# RadioBerry.net
KiCad netlist of a schematic drawn in EAGLE
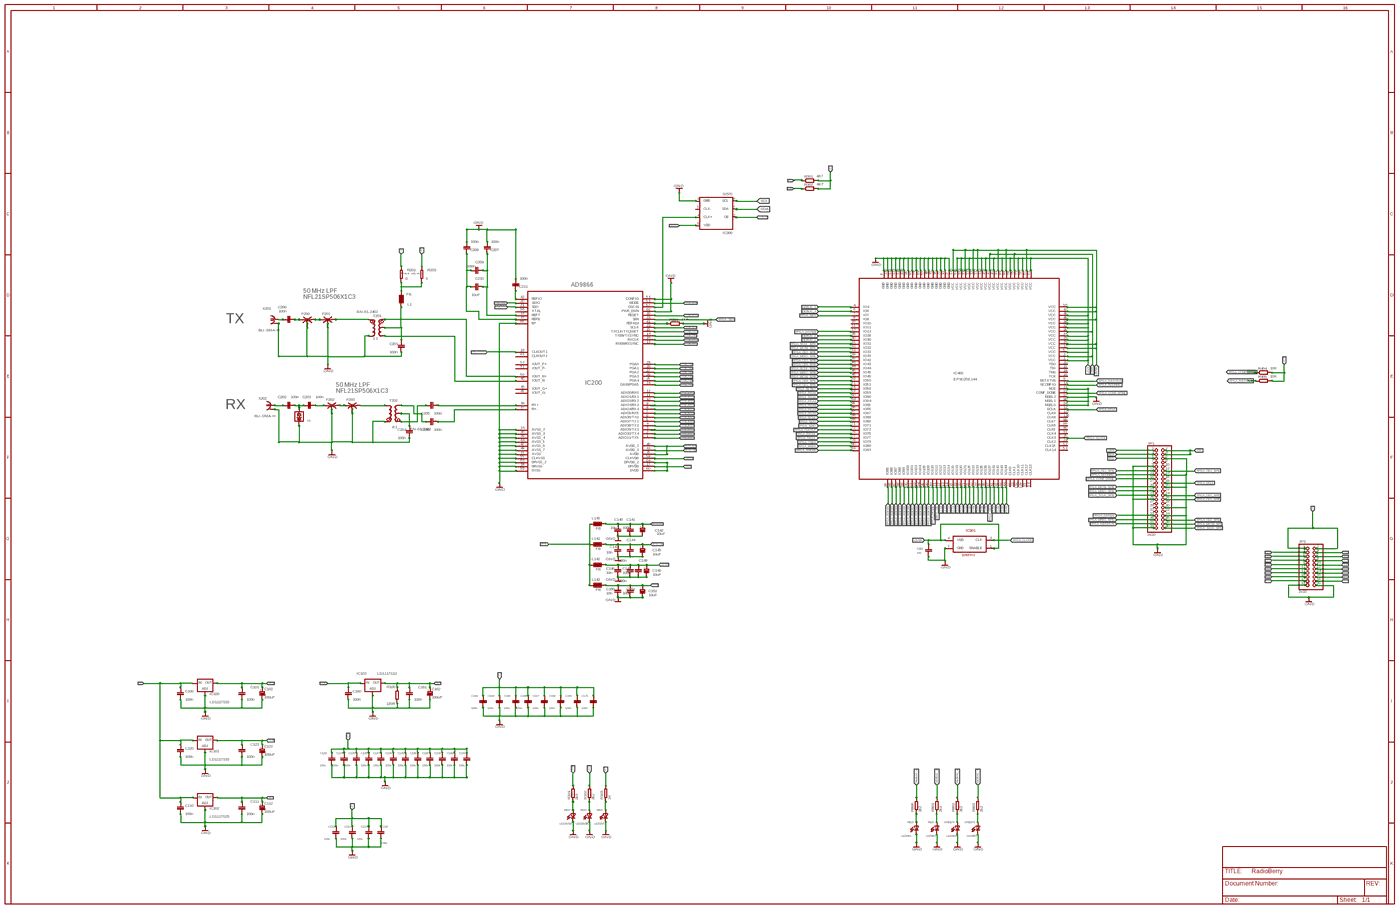
[diagram p0: schematic, sheet 1, overview]
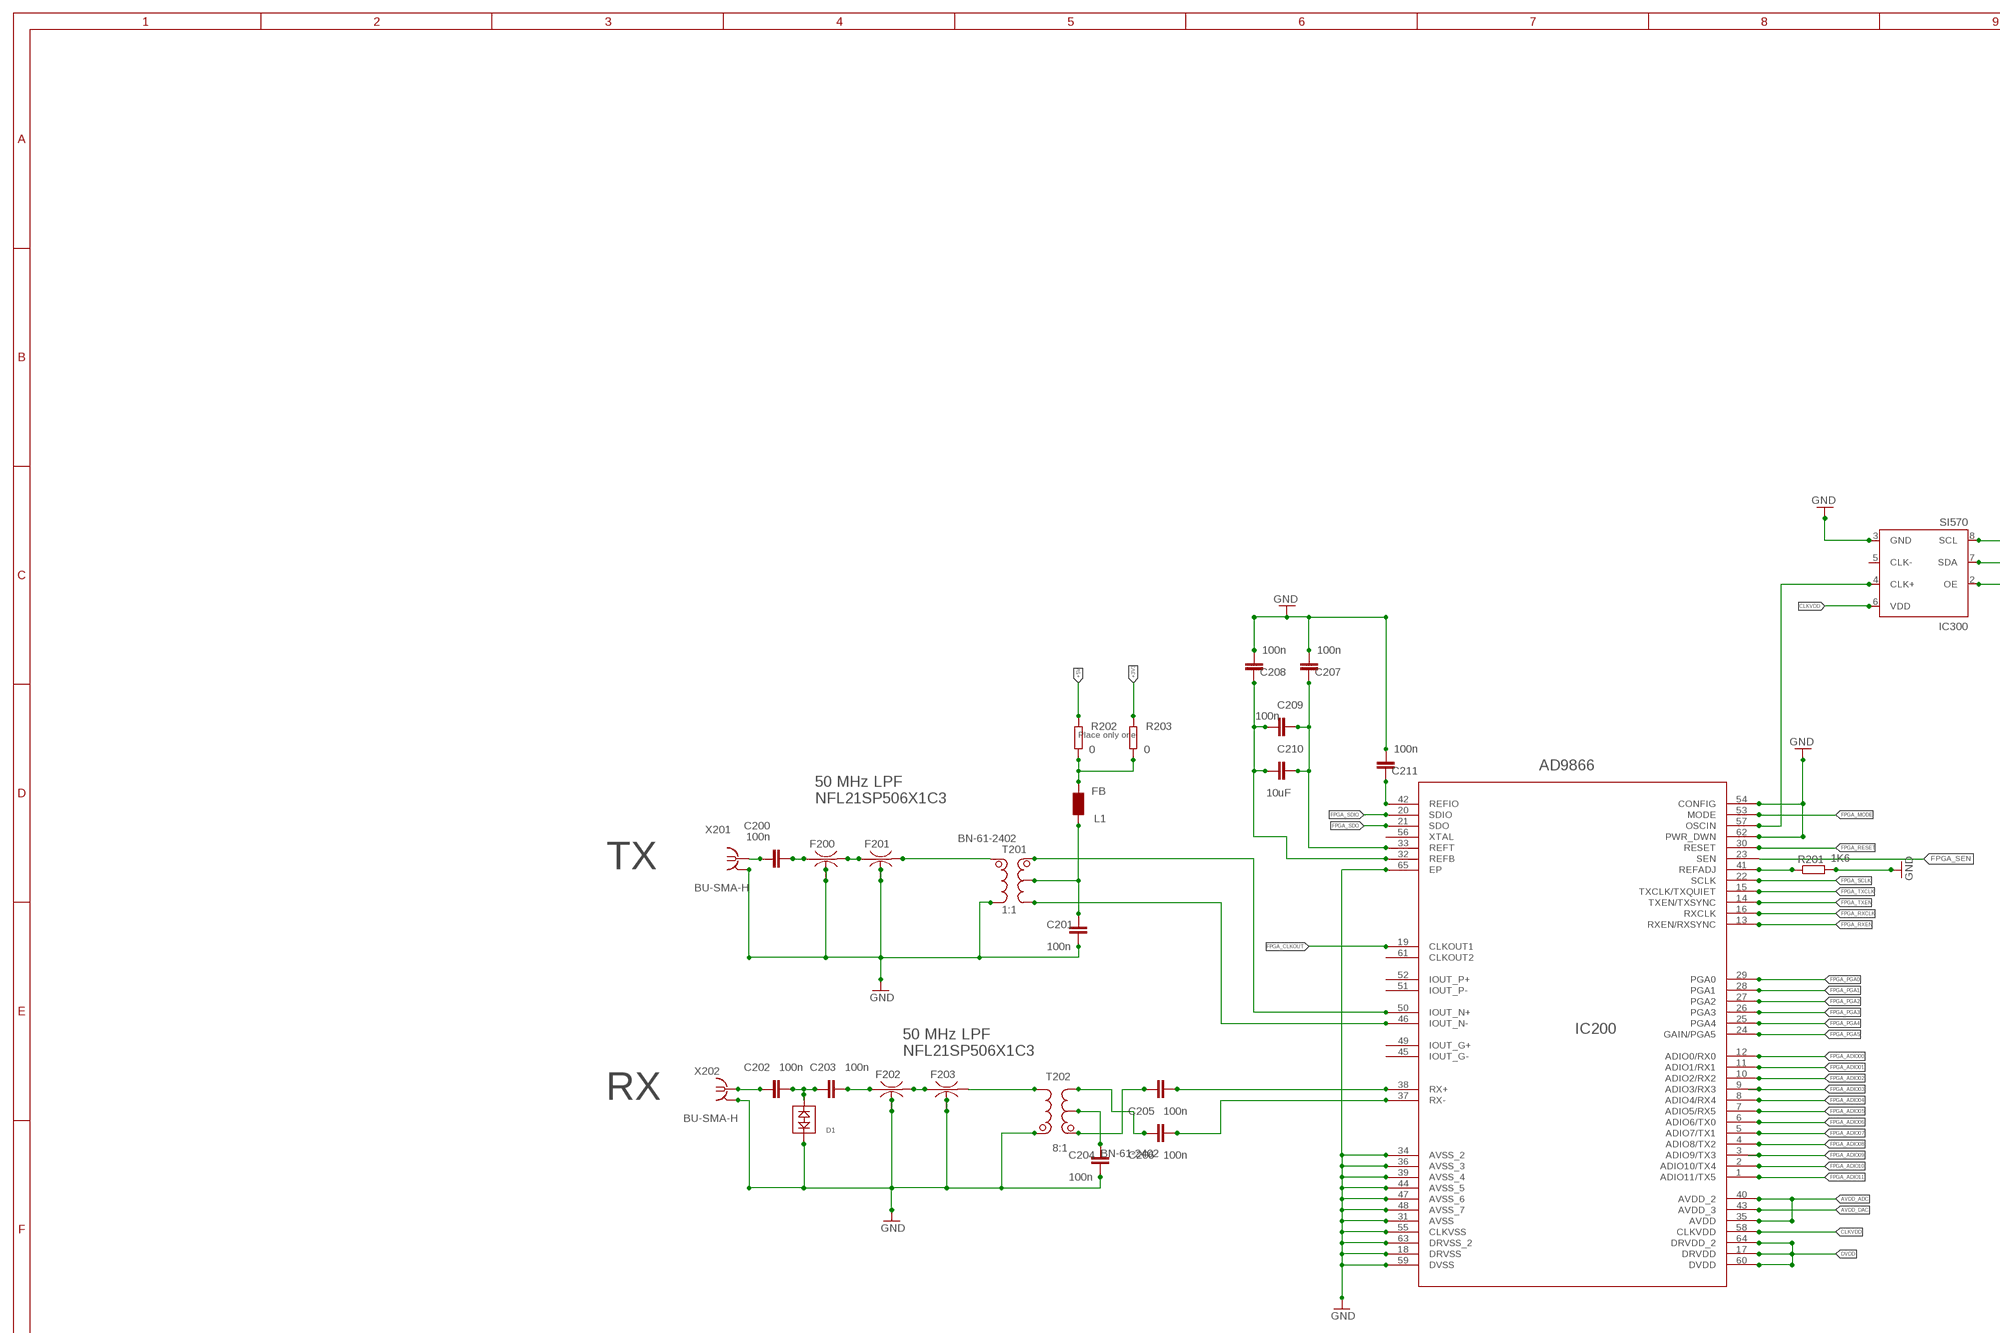
[diagram p1: schematic, sheet 1, part 1 of 4]
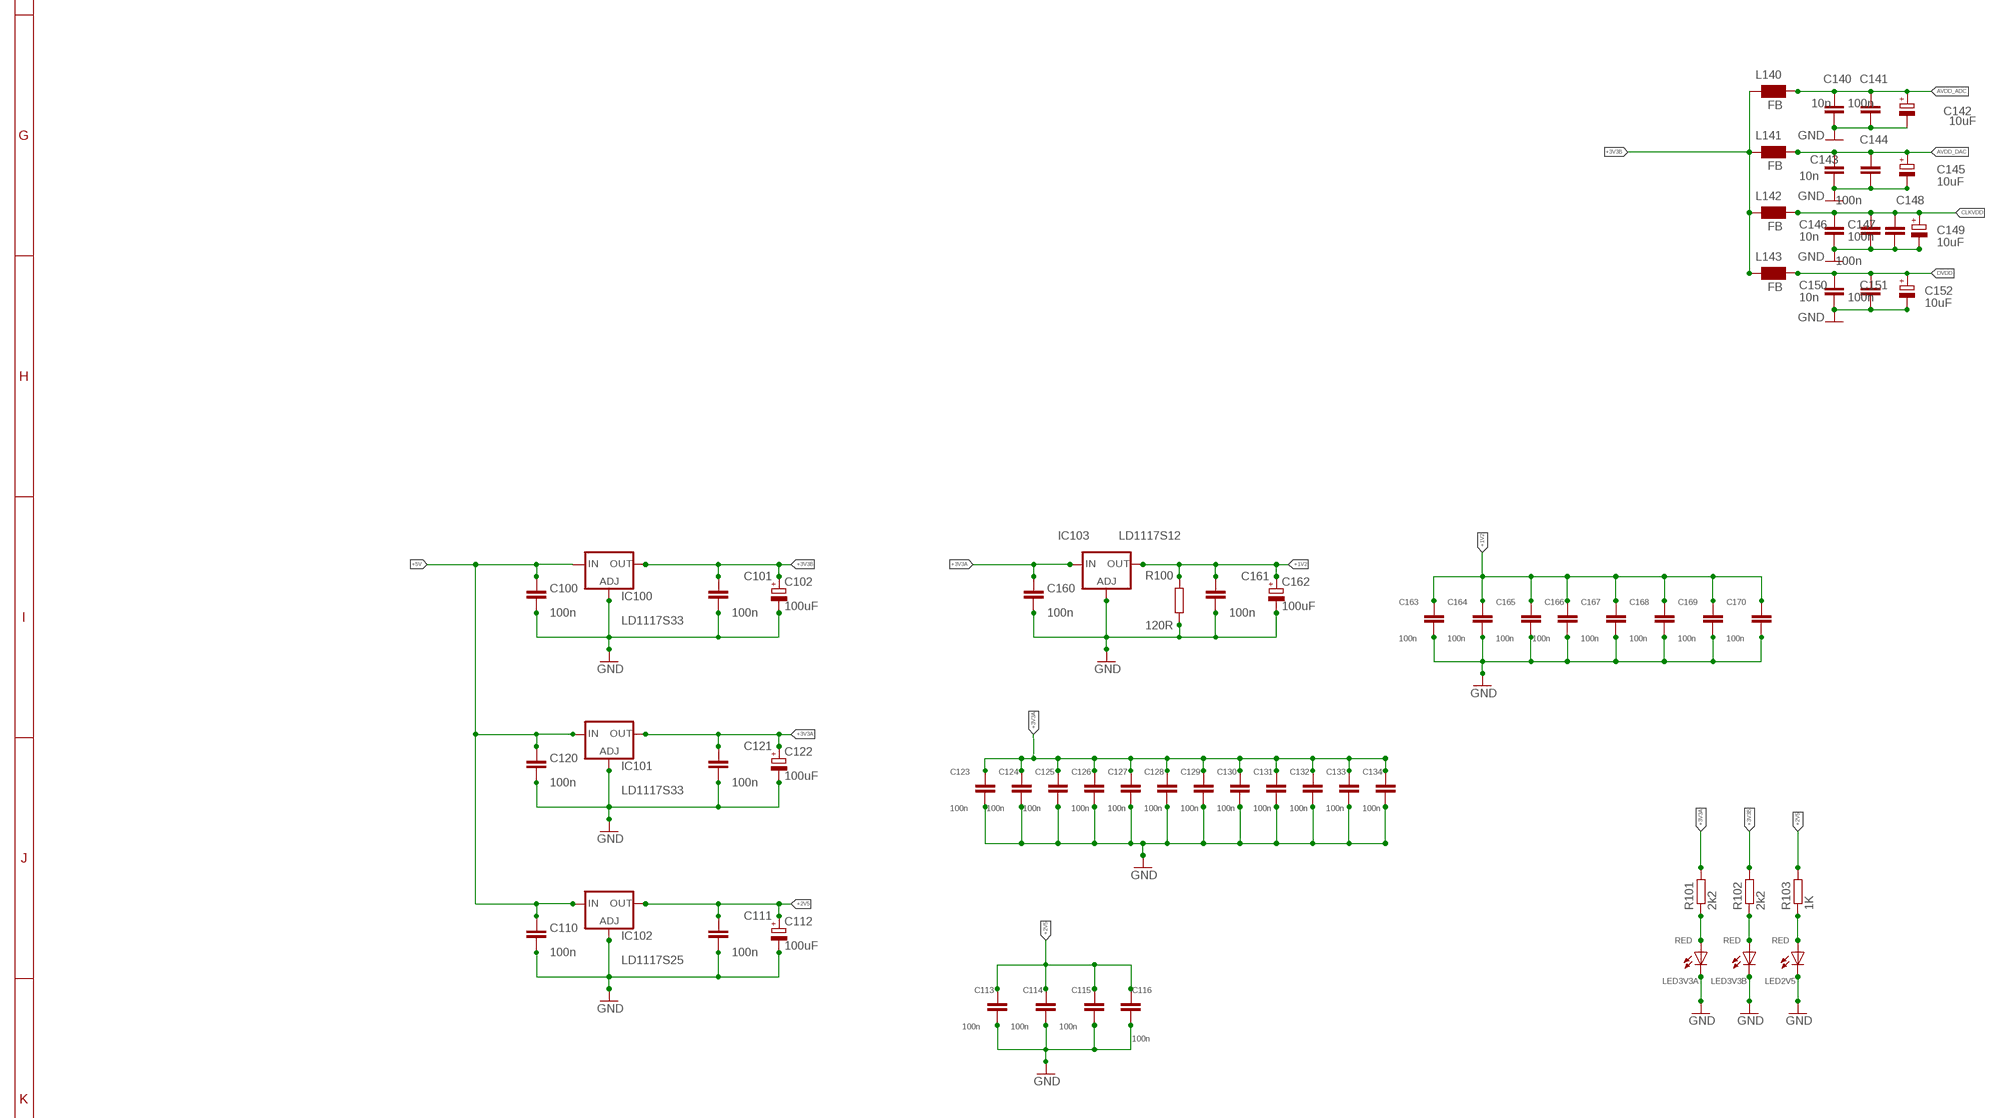
[diagram p2: schematic, sheet 1, part 2 of 4]
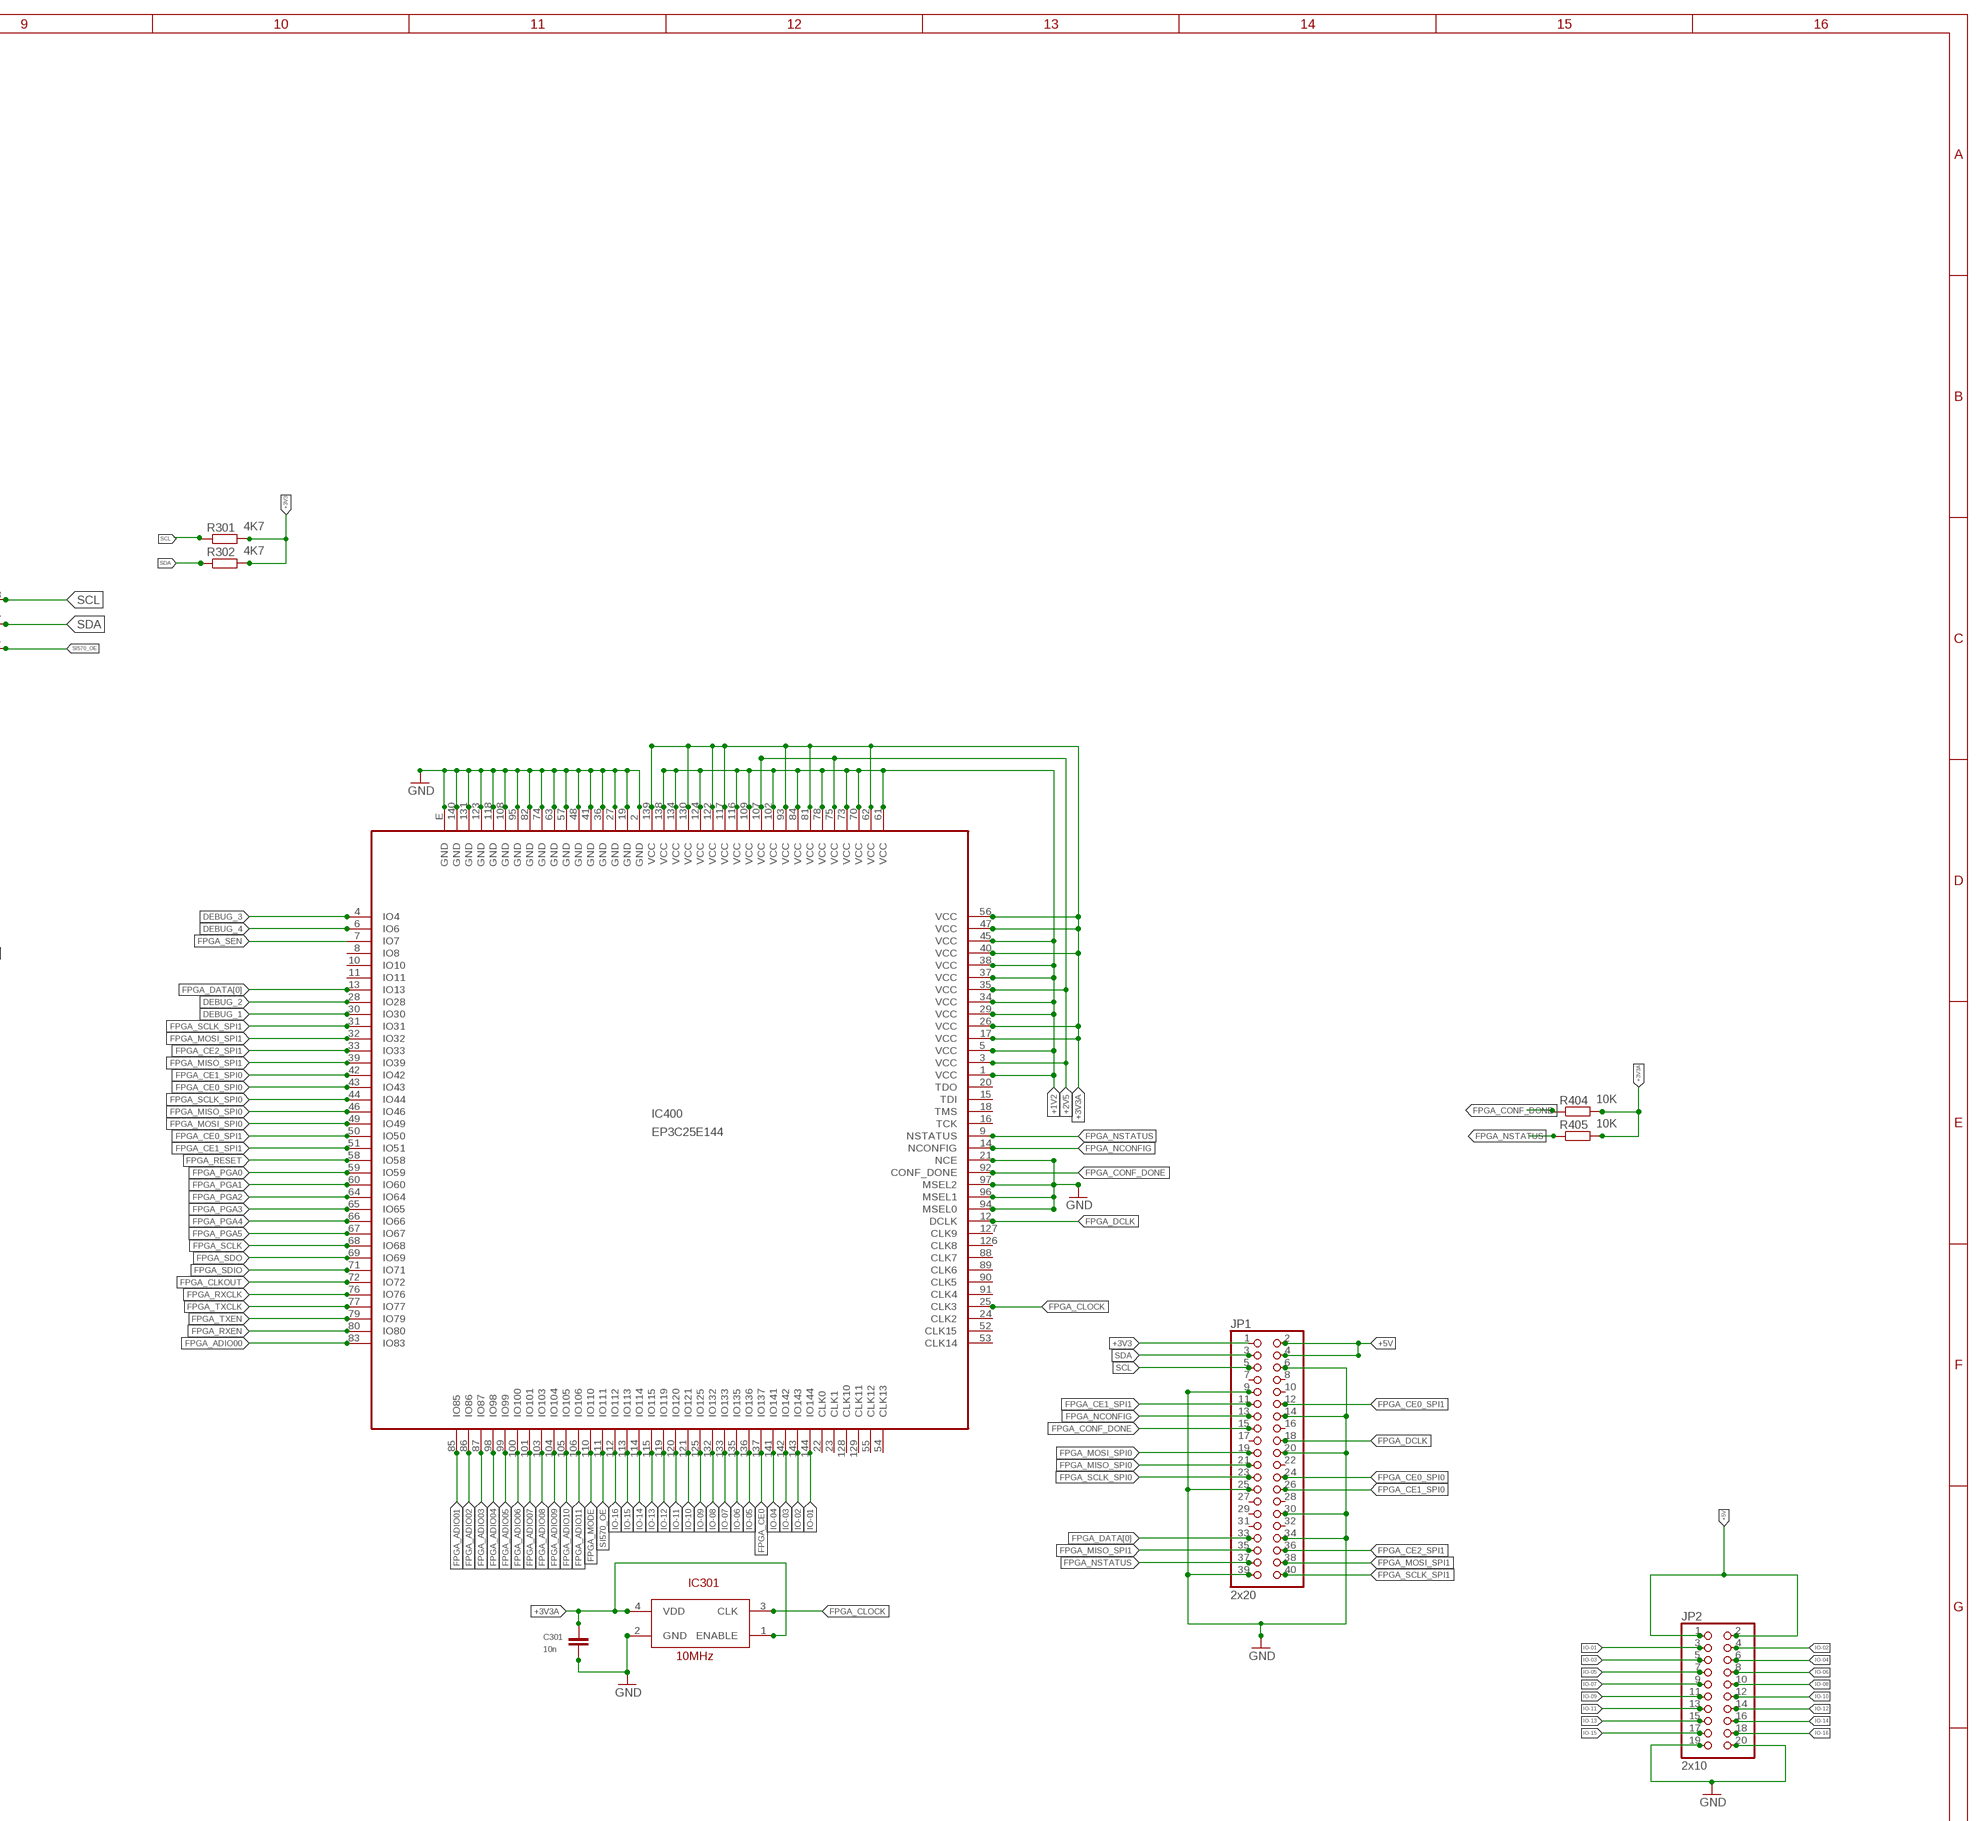
[diagram p3: schematic, sheet 1, part 3 of 4]
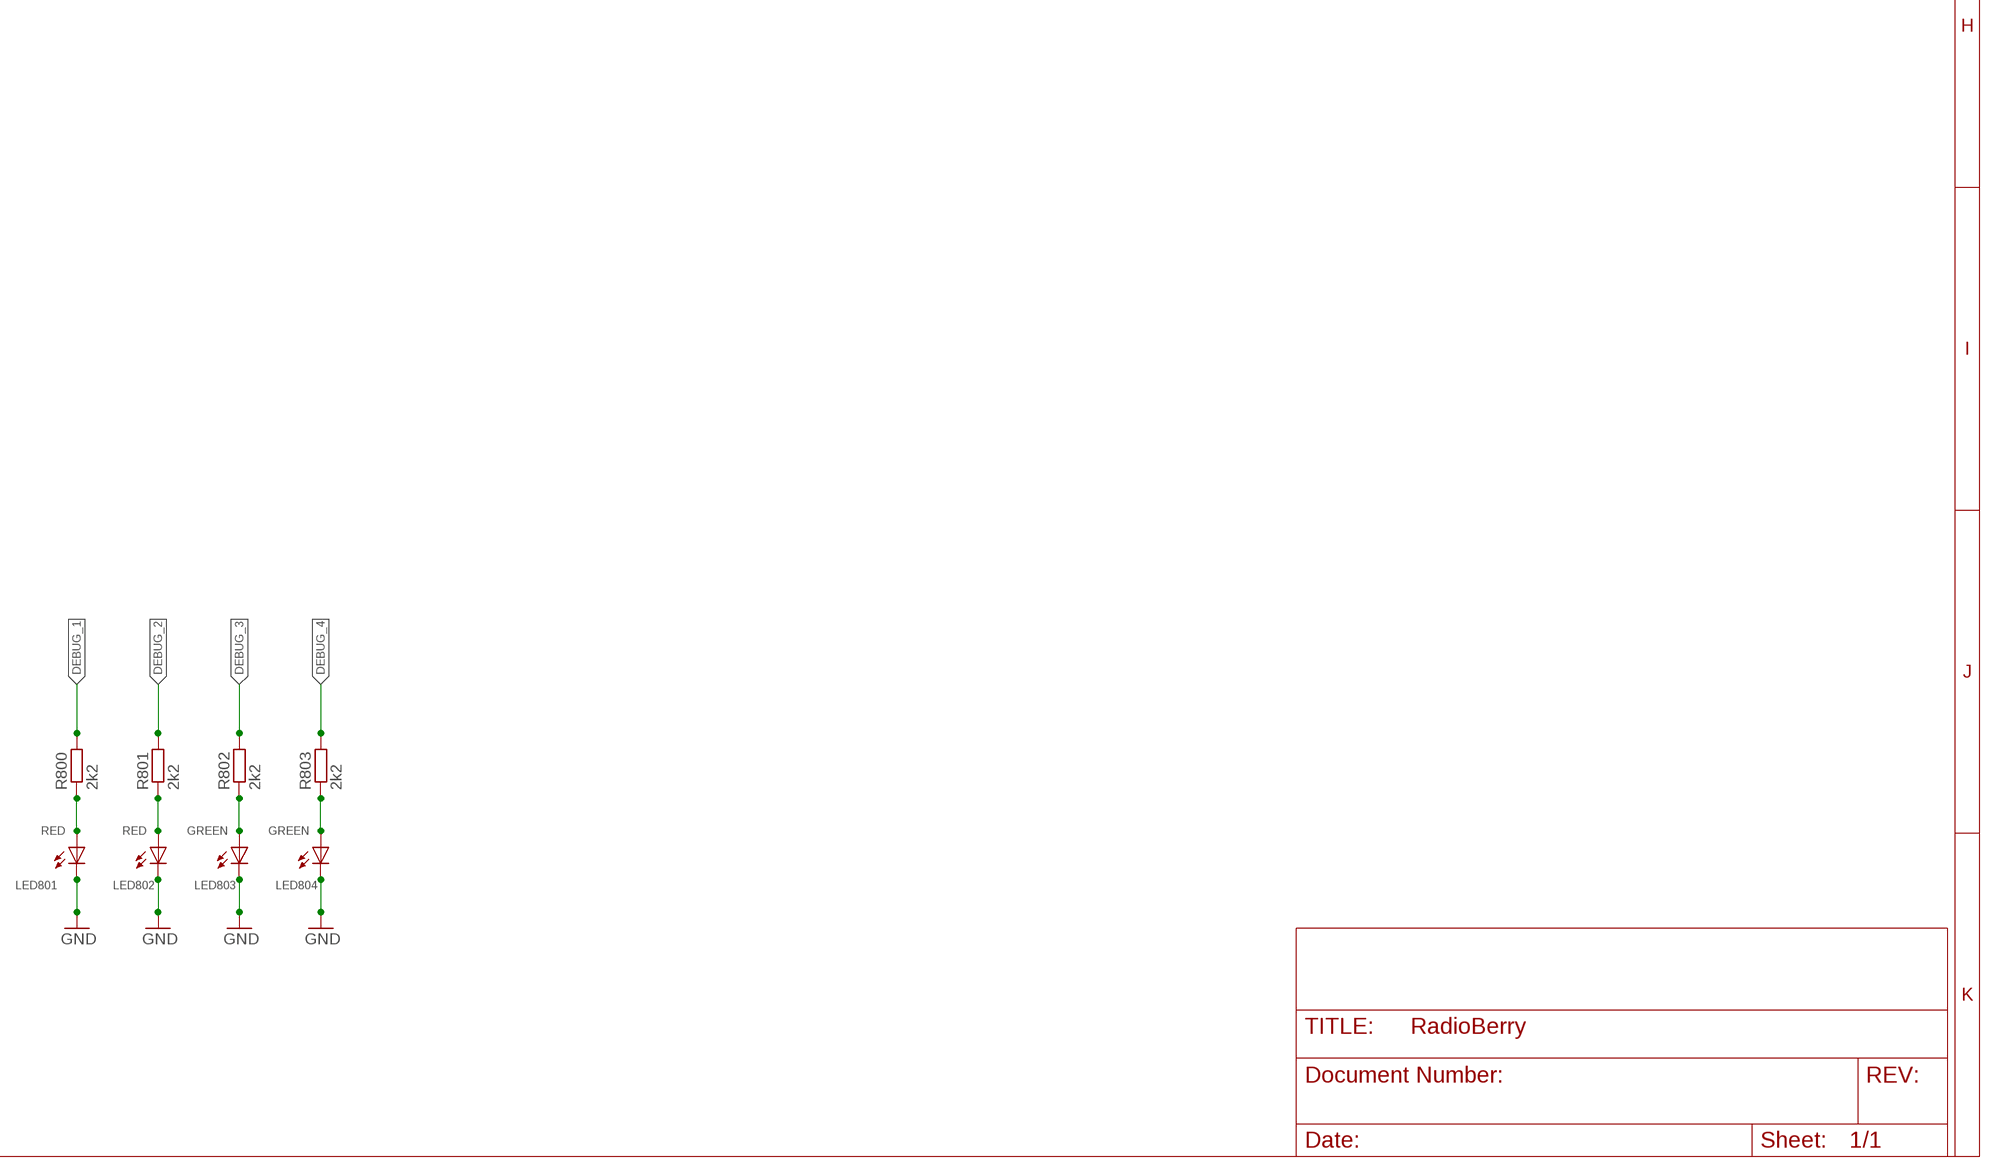
[diagram p4: schematic, sheet 1, part 4 of 4]

(export (version "E")
  (design (tool "Eeschema 10.0.6"))
  (components
    (comp (ref "C100")
      (value "100n")
      (footprint "eagle-import:C0603")
      (libsource (lib "eagle-import") (part "C-EUC0603"))
    )
    (comp (ref "C101")
      (value "100n")
      (footprint "eagle-import:C0603")
      (libsource (lib "eagle-import") (part "C-EUC0603"))
    )
    (comp (ref "C102")
      (value "100uF")
      (footprint "eagle-import:SMC_A")
      (libsource (lib "eagle-import") (part "CPOL-EUSMCA"))
    )
    (comp (ref "C110")
      (value "100n")
      (footprint "eagle-import:C0603")
      (libsource (lib "eagle-import") (part "C-EUC0603"))
    )
    (comp (ref "C111")
      (value "100n")
      (footprint "eagle-import:C0603")
      (libsource (lib "eagle-import") (part "C-EUC0603"))
    )
    (comp (ref "C112")
      (value "100uF")
      (footprint "eagle-import:SMC_A")
      (libsource (lib "eagle-import") (part "CPOL-EUSMCA"))
    )
    (comp (ref "C113")
      (value "100n")
      (footprint "eagle-import:C0603")
      (libsource (lib "eagle-import") (part "C-EUC0603"))
    )
    (comp (ref "C114")
      (value "100n")
      (footprint "eagle-import:C0603")
      (libsource (lib "eagle-import") (part "C-EUC0603"))
    )
    (comp (ref "C115")
      (value "100n")
      (footprint "eagle-import:C0603")
      (libsource (lib "eagle-import") (part "C-EUC0603"))
    )
    (comp (ref "C116")
      (value "100n")
      (footprint "eagle-import:C0603")
      (libsource (lib "eagle-import") (part "C-EUC0603"))
    )
    (comp (ref "C120")
      (value "100n")
      (footprint "eagle-import:C0603")
      (libsource (lib "eagle-import") (part "C-EUC0603"))
    )
    (comp (ref "C121")
      (value "100n")
      (footprint "eagle-import:C0603")
      (libsource (lib "eagle-import") (part "C-EUC0603"))
    )
    (comp (ref "C122")
      (value "100uF")
      (footprint "eagle-import:SMC_A")
      (libsource (lib "eagle-import") (part "CPOL-EUSMCA"))
    )
    (comp (ref "C123")
      (value "100n")
      (footprint "eagle-import:C0603")
      (libsource (lib "eagle-import") (part "C-EUC0603"))
    )
    (comp (ref "C124")
      (value "100n")
      (footprint "eagle-import:C0603")
      (libsource (lib "eagle-import") (part "C-EUC0603"))
    )
    (comp (ref "C125")
      (value "100n")
      (footprint "eagle-import:C0603")
      (libsource (lib "eagle-import") (part "C-EUC0603"))
    )
    (comp (ref "C126")
      (value "100n")
      (footprint "eagle-import:C0603")
      (libsource (lib "eagle-import") (part "C-EUC0603"))
    )
    (comp (ref "C127")
      (value "100n")
      (footprint "eagle-import:C0603")
      (libsource (lib "eagle-import") (part "C-EUC0603"))
    )
    (comp (ref "C128")
      (value "100n")
      (footprint "eagle-import:C0603")
      (libsource (lib "eagle-import") (part "C-EUC0603"))
    )
    (comp (ref "C129")
      (value "100n")
      (footprint "eagle-import:C0603")
      (libsource (lib "eagle-import") (part "C-EUC0603"))
    )
    (comp (ref "C130")
      (value "100n")
      (footprint "eagle-import:C0603")
      (libsource (lib "eagle-import") (part "C-EUC0603"))
    )
    (comp (ref "C131")
      (value "100n")
      (footprint "eagle-import:C0603")
      (libsource (lib "eagle-import") (part "C-EUC0603"))
    )
    (comp (ref "C132")
      (value "100n")
      (footprint "eagle-import:C0603")
      (libsource (lib "eagle-import") (part "C-EUC0603"))
    )
    (comp (ref "C133")
      (value "100n")
      (footprint "eagle-import:C0603")
      (libsource (lib "eagle-import") (part "C-EUC0603"))
    )
    (comp (ref "C134")
      (value "100n")
      (footprint "eagle-import:C0603")
      (libsource (lib "eagle-import") (part "C-EUC0603"))
    )
    (comp (ref "C140")
      (value "10n")
      (footprint "eagle-import:C0603")
      (libsource (lib "eagle-import") (part "C-EUC0603"))
    )
    (comp (ref "C141")
      (value "100n")
      (footprint "eagle-import:C0603")
      (libsource (lib "eagle-import") (part "C-EUC0603"))
    )
    (comp (ref "C142")
      (value "10uF")
      (footprint "eagle-import:SMC_A")
      (libsource (lib "eagle-import") (part "CPOL-EUSMCA"))
    )
    (comp (ref "C143")
      (value "10n")
      (footprint "eagle-import:C0603")
      (libsource (lib "eagle-import") (part "C-EUC0603"))
    )
    (comp (ref "C144")
      (value "100n")
      (footprint "eagle-import:C0603")
      (libsource (lib "eagle-import") (part "C-EUC0603"))
    )
    (comp (ref "C145")
      (value "10uF")
      (footprint "eagle-import:SMC_A")
      (libsource (lib "eagle-import") (part "CPOL-EUSMCA"))
    )
    (comp (ref "C146")
      (value "10n")
      (footprint "eagle-import:C0603")
      (libsource (lib "eagle-import") (part "C-EUC0603"))
    )
    (comp (ref "C147")
      (value "100n")
      (footprint "eagle-import:C0603")
      (libsource (lib "eagle-import") (part "C-EUC0603"))
    )
    (comp (ref "C148")
      (value "100n")
      (footprint "eagle-import:C0603")
      (libsource (lib "eagle-import") (part "C-EUC0603"))
    )
    (comp (ref "C149")
      (value "10uF")
      (footprint "eagle-import:SMC_A")
      (libsource (lib "eagle-import") (part "CPOL-EUSMCA"))
    )
    (comp (ref "C150")
      (value "10n")
      (footprint "eagle-import:C0603")
      (libsource (lib "eagle-import") (part "C-EUC0603"))
    )
    (comp (ref "C151")
      (value "100n")
      (footprint "eagle-import:C0603")
      (libsource (lib "eagle-import") (part "C-EUC0603"))
    )
    (comp (ref "C152")
      (value "10uF")
      (footprint "eagle-import:SMC_A")
      (libsource (lib "eagle-import") (part "CPOL-EUSMCA"))
    )
    (comp (ref "C160")
      (value "100n")
      (footprint "eagle-import:C0603")
      (libsource (lib "eagle-import") (part "C-EUC0603"))
    )
    (comp (ref "C161")
      (value "100n")
      (footprint "eagle-import:C0603")
      (libsource (lib "eagle-import") (part "C-EUC0603"))
    )
    (comp (ref "C162")
      (value "100uF")
      (footprint "eagle-import:SMC_A")
      (libsource (lib "eagle-import") (part "CPOL-EUSMCA"))
    )
    (comp (ref "C163")
      (value "100n")
      (footprint "eagle-import:C0603")
      (libsource (lib "eagle-import") (part "C-EUC0603"))
    )
    (comp (ref "C164")
      (value "100n")
      (footprint "eagle-import:C0603")
      (libsource (lib "eagle-import") (part "C-EUC0603"))
    )
    (comp (ref "C165")
      (value "100n")
      (footprint "eagle-import:C0603")
      (libsource (lib "eagle-import") (part "C-EUC0603"))
    )
    (comp (ref "C166")
      (value "100n")
      (footprint "eagle-import:C0603")
      (libsource (lib "eagle-import") (part "C-EUC0603"))
    )
    (comp (ref "C167")
      (value "100n")
      (footprint "eagle-import:C0603")
      (libsource (lib "eagle-import") (part "C-EUC0603"))
    )
    (comp (ref "C168")
      (value "100n")
      (footprint "eagle-import:C0603")
      (libsource (lib "eagle-import") (part "C-EUC0603"))
    )
    (comp (ref "C169")
      (value "100n")
      (footprint "eagle-import:C0603")
      (libsource (lib "eagle-import") (part "C-EUC0603"))
    )
    (comp (ref "C170")
      (value "100n")
      (footprint "eagle-import:C0603")
      (libsource (lib "eagle-import") (part "C-EUC0603"))
    )
    (comp (ref "C200")
      (value "100n")
      (footprint "eagle-import:C0603")
      (libsource (lib "eagle-import") (part "C-EUC0603"))
    )
    (comp (ref "C201")
      (value "100n")
      (footprint "eagle-import:C0603")
      (libsource (lib "eagle-import") (part "C-EUC0603"))
    )
    (comp (ref "C202")
      (value "100n")
      (footprint "eagle-import:C0603")
      (libsource (lib "eagle-import") (part "C-EUC0603"))
    )
    (comp (ref "C203")
      (value "100n")
      (footprint "eagle-import:C0603")
      (libsource (lib "eagle-import") (part "C-EUC0603"))
    )
    (comp (ref "C204")
      (value "100n")
      (footprint "eagle-import:C0603")
      (libsource (lib "eagle-import") (part "C-EUC0603"))
    )
    (comp (ref "C205")
      (value "100n")
      (footprint "eagle-import:C0603")
      (libsource (lib "eagle-import") (part "C-EUC0603"))
    )
    (comp (ref "C206")
      (value "100n")
      (footprint "eagle-import:C0603")
      (libsource (lib "eagle-import") (part "C-EUC0603"))
    )
    (comp (ref "C207")
      (value "100n")
      (footprint "eagle-import:C0603")
      (libsource (lib "eagle-import") (part "C-EUC0603"))
    )
    (comp (ref "C208")
      (value "100n")
      (footprint "eagle-import:C0603")
      (libsource (lib "eagle-import") (part "C-EUC0603"))
    )
    (comp (ref "C209")
      (value "100n")
      (footprint "eagle-import:C0603")
      (libsource (lib "eagle-import") (part "C-EUC0603"))
    )
    (comp (ref "C210")
      (value "10uF")
      (footprint "eagle-import:C1206")
      (libsource (lib "eagle-import") (part "C-EUC1206"))
    )
    (comp (ref "C211")
      (value "100n")
      (footprint "eagle-import:C0603")
      (libsource (lib "eagle-import") (part "C-EUC0603"))
    )
    (comp (ref "C301")
      (value "10n")
      (footprint "eagle-import:C0603")
      (libsource (lib "eagle-import") (part "C-EUC0603"))
    )
    (comp (ref "D1")
      (value "GBLC03C")
      (footprint "eagle-import:SOD-323")
      (libsource (lib "eagle-import") (part "GBLC03C"))
    )
    (comp (ref "F200")
      (value "NFM21C")
      (footprint "eagle-import:NFM21C")
      (libsource (lib "eagle-import") (part "NFM21C"))
    )
    (comp (ref "F201")
      (value "NFM21C")
      (footprint "eagle-import:NFM21C")
      (libsource (lib "eagle-import") (part "NFM21C"))
    )
    (comp (ref "F202")
      (value "NFM21C")
      (footprint "eagle-import:NFM21C")
      (libsource (lib "eagle-import") (part "NFM21C"))
    )
    (comp (ref "F203")
      (value "NFM21C")
      (footprint "eagle-import:NFM21C")
      (libsource (lib "eagle-import") (part "NFM21C"))
    )
    (comp (ref "IC100")
      (value "LD1117S33")
      (footprint "eagle-import:SOT223")
      (libsource (lib "eagle-import") (part "LD117A?S33TR"))
    )
    (comp (ref "IC101")
      (value "LD1117S33")
      (footprint "eagle-import:SOT223")
      (libsource (lib "eagle-import") (part "LD117A?S33TR"))
    )
    (comp (ref "IC102")
      (value "LD1117S25")
      (footprint "eagle-import:SOT223")
      (libsource (lib "eagle-import") (part "LD117A?S33TR"))
    )
    (comp (ref "IC103")
      (value "LD1117S12")
      (footprint "eagle-import:SOT223")
      (libsource (lib "eagle-import") (part "LD117A?S12TR"))
    )
    (comp (ref "IC200")
      (value "AD9866")
      (footprint "eagle-import:CP_64_3")
      (libsource (lib "eagle-import") (part "AD9866"))
    )
    (comp (ref "IC300")
      (value "SI570")
      (footprint "eagle-import:8-PIN")
      (libsource (lib "eagle-import") (part "SI570"))
    )
    (comp (ref "IC301")
      (value "10MHz")
      (footprint "eagle-import:MODEL625")
      (libsource (lib "eagle-import") (part "CLOCK"))
    )
    (comp (ref "IC400")
      (value "EP3C25E144")
      (footprint "eagle-import:EQFP144")
      (fields (field (name "MPN") "EP3C25E144C8N"))
      (libsource (lib "eagle-import") (part "EP3C25E144"))
    )
    (comp (ref "JP1")
      (value "2x20")
      (footprint "eagle-import:2X20")
      (libsource (lib "eagle-import") (part "PINHD-2X20"))
    )
    (comp (ref "JP2")
      (value "2x10")
      (footprint "eagle-import:2X10")
      (libsource (lib "eagle-import") (part "PINHD-2X10"))
    )
    (comp (ref "L1")
      (value "FB")
      (footprint "eagle-import:0805")
      (libsource (lib "eagle-import") (part "WE-CBF_0805"))
    )
    (comp (ref "L140")
      (value "FB")
      (footprint "eagle-import:0805")
      (libsource (lib "eagle-import") (part "WE-CBF_0805"))
    )
    (comp (ref "L141")
      (value "FB")
      (footprint "eagle-import:0805")
      (libsource (lib "eagle-import") (part "WE-CBF_0805"))
    )
    (comp (ref "L142")
      (value "FB")
      (footprint "eagle-import:0805")
      (libsource (lib "eagle-import") (part "WE-CBF_0805"))
    )
    (comp (ref "L143")
      (value "FB")
      (footprint "eagle-import:0805")
      (libsource (lib "eagle-import") (part "WE-CBF_0805"))
    )
    (comp (ref "LED2V5")
      (value "RED")
      (footprint "eagle-import:CHIP-LED0805")
      (libsource (lib "eagle-import") (part "LEDCHIP-LED0805"))
    )
    (comp (ref "LED3V3A")
      (value "RED")
      (footprint "eagle-import:CHIP-LED0805")
      (libsource (lib "eagle-import") (part "LEDCHIP-LED0805"))
    )
    (comp (ref "LED3V3B")
      (value "RED")
      (footprint "eagle-import:CHIP-LED0805")
      (libsource (lib "eagle-import") (part "LEDCHIP-LED0805"))
    )
    (comp (ref "LED801")
      (value "RED")
      (footprint "eagle-import:CHIP-LED0805")
      (libsource (lib "eagle-import") (part "LEDCHIP-LED0805"))
    )
    (comp (ref "LED802")
      (value "RED")
      (footprint "eagle-import:CHIP-LED0805")
      (libsource (lib "eagle-import") (part "LEDCHIP-LED0805"))
    )
    (comp (ref "LED803")
      (value "GREEN")
      (footprint "eagle-import:CHIP-LED0805")
      (libsource (lib "eagle-import") (part "LEDCHIP-LED0805"))
    )
    (comp (ref "LED804")
      (value "GREEN")
      (footprint "eagle-import:CHIP-LED0805")
      (libsource (lib "eagle-import") (part "LEDCHIP-LED0805"))
    )
    (comp (ref "R100")
      (value "120R")
      (footprint "eagle-import:R0805")
      (libsource (lib "eagle-import") (part "R-EU_R0805"))
    )
    (comp (ref "R101")
      (value "2k2")
      (footprint "eagle-import:R0805")
      (libsource (lib "eagle-import") (part "R-EU_R0805"))
    )
    (comp (ref "R102")
      (value "2k2")
      (footprint "eagle-import:R0805")
      (libsource (lib "eagle-import") (part "R-EU_R0805"))
    )
    (comp (ref "R103")
      (value "1K")
      (footprint "eagle-import:R0805")
      (libsource (lib "eagle-import") (part "R-EU_R0805"))
    )
    (comp (ref "R201")
      (value "1K6")
      (footprint "eagle-import:R0805")
      (libsource (lib "eagle-import") (part "R-EU_R0805"))
    )
    (comp (ref "R202")
      (value "0")
      (footprint "eagle-import:R0805")
      (libsource (lib "eagle-import") (part "R-EU_R0805"))
    )
    (comp (ref "R203")
      (value "0")
      (footprint "eagle-import:R0805")
      (libsource (lib "eagle-import") (part "R-EU_R0805"))
    )
    (comp (ref "R301")
      (value "4K7")
      (footprint "eagle-import:R0805")
      (libsource (lib "eagle-import") (part "R-EU_R0805"))
    )
    (comp (ref "R302")
      (value "4K7")
      (footprint "eagle-import:R0805")
      (libsource (lib "eagle-import") (part "R-EU_R0805"))
    )
    (comp (ref "R404")
      (value "10K")
      (footprint "eagle-import:R0805")
      (libsource (lib "eagle-import") (part "R-EU_R0805"))
    )
    (comp (ref "R405")
      (value "10K")
      (footprint "eagle-import:R0805")
      (libsource (lib "eagle-import") (part "R-EU_R0805"))
    )
    (comp (ref "R800")
      (value "2k2")
      (footprint "eagle-import:R0805")
      (libsource (lib "eagle-import") (part "R-EU_R0805"))
    )
    (comp (ref "R801")
      (value "2k2")
      (footprint "eagle-import:R0805")
      (libsource (lib "eagle-import") (part "R-EU_R0805"))
    )
    (comp (ref "R802")
      (value "2k2")
      (footprint "eagle-import:R0805")
      (libsource (lib "eagle-import") (part "R-EU_R0805"))
    )
    (comp (ref "R803")
      (value "2k2")
      (footprint "eagle-import:R0805")
      (libsource (lib "eagle-import") (part "R-EU_R0805"))
    )
    (comp (ref "T201")
      (value "BN-61-2402")
      (footprint "eagle-import:DIL06")
      (libsource (lib "eagle-import") (part "T1-1TDIL"))
    )
    (comp (ref "T202")
      (value "BN-61-2402")
      (footprint "eagle-import:DIL06")
      (libsource (lib "eagle-import") (part "T1-1TDIL"))
    )
    (comp (ref "X201")
      (value "BU-SMA-H")
      (footprint "eagle-import:BU-SMA-H")
      (libsource (lib "eagle-import") (part "BU-SMA-H"))
    )
    (comp (ref "X202")
      (value "BU-SMA-H")
      (footprint "eagle-import:BU-SMA-H")
      (libsource (lib "eagle-import") (part "BU-SMA-H"))
    )
  )
  (nets
    (net (code "1") (name "+1V2") (class "Default")
      (node (ref "C161") (pin "2") (pinfunction "2_2") (pintype "passive"))
      (node (ref "C162") (pin "+") (pinfunction "+_+") (pintype "passive"))
      (node (ref "C163") (pin "2") (pinfunction "2_2") (pintype "passive"))
      (node (ref "C164") (pin "2") (pinfunction "2_2") (pintype "passive"))
      (node (ref "C165") (pin "2") (pinfunction "2_2") (pintype "passive"))
      (node (ref "C166") (pin "2") (pinfunction "2_2") (pintype "passive"))
      (node (ref "C167") (pin "2") (pinfunction "2_2") (pintype "passive"))
      (node (ref "C168") (pin "2") (pinfunction "2_2") (pintype "passive"))
      (node (ref "C169") (pin "2") (pinfunction "2_2") (pintype "passive"))
      (node (ref "C170") (pin "2") (pinfunction "2_2") (pintype "passive"))
      (node (ref "IC103") (pin "4") (pinfunction "OUT_4") (pintype "passive"))
      (node (ref "IC400") (pin "1") (pinfunction "VCC_1") (pintype "power_in"))
      (node (ref "IC400") (pin "102") (pinfunction "VCC_102") (pintype "power_in"))
      (node (ref "IC400") (pin "109") (pinfunction "VCC_109") (pintype "power_in"))
      (node (ref "IC400") (pin "116") (pinfunction "VCC_116") (pintype "power_in"))
      (node (ref "IC400") (pin "124") (pinfunction "VCC_124") (pintype "power_in"))
      (node (ref "IC400") (pin "134") (pinfunction "VCC_134") (pintype "power_in"))
      (node (ref "IC400") (pin "138") (pinfunction "VCC_138") (pintype "power_in"))
      (node (ref "IC400") (pin "29") (pinfunction "VCC_29") (pintype "power_in"))
      (node (ref "IC400") (pin "34") (pinfunction "VCC_34") (pintype "power_in"))
      (node (ref "IC400") (pin "37") (pinfunction "VCC_37") (pintype "power_in"))
      (node (ref "IC400") (pin "38") (pinfunction "VCC_38") (pintype "power_in"))
      (node (ref "IC400") (pin "45") (pinfunction "VCC_45") (pintype "power_in"))
      (node (ref "IC400") (pin "5") (pinfunction "VCC_5") (pintype "power_in"))
      (node (ref "IC400") (pin "61") (pinfunction "VCC_61") (pintype "power_in"))
      (node (ref "IC400") (pin "70") (pinfunction "VCC_70") (pintype "power_in"))
      (node (ref "IC400") (pin "73") (pinfunction "VCC_73") (pintype "power_in"))
      (node (ref "IC400") (pin "78") (pinfunction "VCC_78") (pintype "power_in"))
      (node (ref "IC400") (pin "84") (pinfunction "VCC_84") (pintype "power_in"))
      (node (ref "R100") (pin "2") (pinfunction "2_2") (pintype "passive"))
    )
    (net (code "2") (name "+2V5") (class "Default")
      (node (ref "C111") (pin "2") (pinfunction "2_2") (pintype "passive"))
      (node (ref "C112") (pin "+") (pinfunction "+_+") (pintype "passive"))
      (node (ref "C113") (pin "2") (pinfunction "2_2") (pintype "passive"))
      (node (ref "C114") (pin "2") (pinfunction "2_2") (pintype "passive"))
      (node (ref "C115") (pin "2") (pinfunction "2_2") (pintype "passive"))
      (node (ref "C116") (pin "2") (pinfunction "2_2") (pintype "passive"))
      (node (ref "IC102") (pin "4") (pinfunction "OUT_4") (pintype "passive"))
      (node (ref "IC400") (pin "107") (pinfunction "VCC_107") (pintype "power_in"))
      (node (ref "IC400") (pin "3") (pinfunction "VCC_3") (pintype "power_in"))
      (node (ref "IC400") (pin "35") (pinfunction "VCC_35") (pintype "power_in"))
      (node (ref "IC400") (pin "75") (pinfunction "VCC_75") (pintype "power_in"))
      (node (ref "R103") (pin "2") (pinfunction "2_2") (pintype "passive"))
    )
    (net (code "3") (name "+3V3") (class "Default")
      (node (ref "JP1") (pin "1") (pinfunction "1_1") (pintype "passive"))
      (node (ref "R203") (pin "2") (pinfunction "2_2") (pintype "passive"))
      (node (ref "R301") (pin "2") (pinfunction "2_2") (pintype "passive"))
      (node (ref "R302") (pin "2") (pinfunction "2_2") (pintype "passive"))
    )
    (net (code "4") (name "+3V3A") (class "Default")
      (node (ref "C121") (pin "2") (pinfunction "2_2") (pintype "passive"))
      (node (ref "C122") (pin "+") (pinfunction "+_+") (pintype "passive"))
      (node (ref "C123") (pin "2") (pinfunction "2_2") (pintype "passive"))
      (node (ref "C124") (pin "2") (pinfunction "2_2") (pintype "passive"))
      (node (ref "C125") (pin "2") (pinfunction "2_2") (pintype "passive"))
      (node (ref "C126") (pin "2") (pinfunction "2_2") (pintype "passive"))
      (node (ref "C127") (pin "2") (pinfunction "2_2") (pintype "passive"))
      (node (ref "C128") (pin "2") (pinfunction "2_2") (pintype "passive"))
      (node (ref "C129") (pin "2") (pinfunction "2_2") (pintype "passive"))
      (node (ref "C130") (pin "2") (pinfunction "2_2") (pintype "passive"))
      (node (ref "C131") (pin "2") (pinfunction "2_2") (pintype "passive"))
      (node (ref "C132") (pin "2") (pinfunction "2_2") (pintype "passive"))
      (node (ref "C133") (pin "2") (pinfunction "2_2") (pintype "passive"))
      (node (ref "C134") (pin "2") (pinfunction "2_2") (pintype "passive"))
      (node (ref "C160") (pin "2") (pinfunction "2_2") (pintype "passive"))
      (node (ref "C301") (pin "2") (pinfunction "2_2") (pintype "passive"))
      (node (ref "IC101") (pin "4") (pinfunction "OUT_4") (pintype "passive"))
      (node (ref "IC103") (pin "3") (pinfunction "IN_3") (pintype "input"))
      (node (ref "IC301") (pin "1") (pinfunction "ENABLE_1") (pintype "input"))
      (node (ref "IC301") (pin "4") (pinfunction "VDD_4") (pintype "power_in"))
      (node (ref "IC400") (pin "117") (pinfunction "VCC_117") (pintype "power_in"))
      (node (ref "IC400") (pin "122") (pinfunction "VCC_122") (pintype "power_in"))
      (node (ref "IC400") (pin "130") (pinfunction "VCC_130") (pintype "power_in"))
      (node (ref "IC400") (pin "139") (pinfunction "VCC_139") (pintype "power_in"))
      (node (ref "IC400") (pin "17") (pinfunction "VCC_17") (pintype "power_in"))
      (node (ref "IC400") (pin "26") (pinfunction "VCC_26") (pintype "power_in"))
      (node (ref "IC400") (pin "40") (pinfunction "VCC_40") (pintype "power_in"))
      (node (ref "IC400") (pin "47") (pinfunction "VCC_47") (pintype "power_in"))
      (node (ref "IC400") (pin "56") (pinfunction "VCC_56") (pintype "power_in"))
      (node (ref "IC400") (pin "62") (pinfunction "VCC_62") (pintype "power_in"))
      (node (ref "IC400") (pin "81") (pinfunction "VCC_81") (pintype "power_in"))
      (node (ref "IC400") (pin "93") (pinfunction "VCC_93") (pintype "power_in"))
      (node (ref "R101") (pin "2") (pinfunction "2_2") (pintype "passive"))
      (node (ref "R404") (pin "2") (pinfunction "2_2") (pintype "passive"))
      (node (ref "R405") (pin "2") (pinfunction "2_2") (pintype "passive"))
    )
    (net (code "5") (name "+3V3B") (class "Default")
      (node (ref "C101") (pin "2") (pinfunction "2_2") (pintype "passive"))
      (node (ref "C102") (pin "+") (pinfunction "+_+") (pintype "passive"))
      (node (ref "IC100") (pin "4") (pinfunction "OUT_4") (pintype "passive"))
      (node (ref "L140") (pin "1") (pinfunction "1_1") (pintype "passive"))
      (node (ref "L141") (pin "1") (pinfunction "1_1") (pintype "passive"))
      (node (ref "L142") (pin "1") (pinfunction "1_1") (pintype "passive"))
      (node (ref "L143") (pin "1") (pinfunction "1_1") (pintype "passive"))
      (node (ref "R102") (pin "2") (pinfunction "2_2") (pintype "passive"))
    )
    (net (code "6") (name "+5V") (class "Default")
      (node (ref "C100") (pin "2") (pinfunction "2_2") (pintype "passive"))
      (node (ref "C110") (pin "2") (pinfunction "2_2") (pintype "passive"))
      (node (ref "C120") (pin "2") (pinfunction "2_2") (pintype "passive"))
      (node (ref "IC100") (pin "3") (pinfunction "IN_3") (pintype "input"))
      (node (ref "IC101") (pin "3") (pinfunction "IN_3") (pintype "input"))
      (node (ref "IC102") (pin "3") (pinfunction "IN_3") (pintype "input"))
      (node (ref "JP1") (pin "2") (pinfunction "2_2") (pintype "passive"))
      (node (ref "JP1") (pin "4") (pinfunction "4_4") (pintype "passive"))
      (node (ref "JP2") (pin "1") (pinfunction "1_1") (pintype "passive"))
      (node (ref "JP2") (pin "2") (pinfunction "2_2") (pintype "passive"))
      (node (ref "R202") (pin "2") (pinfunction "2_2") (pintype "passive"))
    )
    (net (code "7") (name "AVDD_ADC") (class "Default")
      (node (ref "C140") (pin "2") (pinfunction "2_2") (pintype "passive"))
      (node (ref "C141") (pin "2") (pinfunction "2_2") (pintype "passive"))
      (node (ref "C142") (pin "+") (pinfunction "+_+") (pintype "passive"))
      (node (ref "IC200") (pin "35") (pinfunction "AVDD_35") (pintype "power_in"))
      (node (ref "IC200") (pin "40") (pinfunction "AVDD_2_40") (pintype "power_in"))
      (node (ref "L140") (pin "2") (pinfunction "2_2") (pintype "passive"))
    )
    (net (code "8") (name "AVDD_DAC") (class "Default")
      (node (ref "C143") (pin "2") (pinfunction "2_2") (pintype "passive"))
      (node (ref "C144") (pin "2") (pinfunction "2_2") (pintype "passive"))
      (node (ref "C145") (pin "+") (pinfunction "+_+") (pintype "passive"))
      (node (ref "IC200") (pin "43") (pinfunction "AVDD_3_43") (pintype "power_in"))
      (node (ref "L141") (pin "2") (pinfunction "2_2") (pintype "passive"))
    )
    (net (code "9") (name "CLKVDD") (class "Default")
      (node (ref "C146") (pin "2") (pinfunction "2_2") (pintype "passive"))
      (node (ref "C147") (pin "2") (pinfunction "2_2") (pintype "passive"))
      (node (ref "C148") (pin "2") (pinfunction "2_2") (pintype "passive"))
      (node (ref "C149") (pin "+") (pinfunction "+_+") (pintype "passive"))
      (node (ref "IC200") (pin "58") (pinfunction "CLKVDD_58") (pintype "power_in"))
      (node (ref "IC300") (pin "6") (pinfunction "VDD_6") (pintype "power_in"))
      (node (ref "L142") (pin "2") (pinfunction "2_2") (pintype "passive"))
    )
    (net (code "10") (name "DEBUG_1") (class "Default")
      (node (ref "IC400") (pin "30") (pinfunction "IO30_30") (pintype "bidirectional"))
      (node (ref "R800") (pin "2") (pinfunction "2_2") (pintype "passive"))
    )
    (net (code "11") (name "DEBUG_2") (class "Default")
      (node (ref "IC400") (pin "28") (pinfunction "IO28_28") (pintype "bidirectional"))
      (node (ref "R801") (pin "2") (pinfunction "2_2") (pintype "passive"))
    )
    (net (code "12") (name "DEBUG_3") (class "Default")
      (node (ref "IC400") (pin "4") (pinfunction "IO4_4") (pintype "passive"))
      (node (ref "R802") (pin "2") (pinfunction "2_2") (pintype "passive"))
    )
    (net (code "13") (name "DEBUG_4") (class "Default")
      (node (ref "IC400") (pin "6") (pinfunction "IO6_6") (pintype "passive"))
      (node (ref "R803") (pin "2") (pinfunction "2_2") (pintype "passive"))
    )
    (net (code "14") (name "DVDD") (class "Default")
      (node (ref "C150") (pin "2") (pinfunction "2_2") (pintype "passive"))
      (node (ref "C151") (pin "2") (pinfunction "2_2") (pintype "passive"))
      (node (ref "C152") (pin "+") (pinfunction "+_+") (pintype "passive"))
      (node (ref "IC200") (pin "17") (pinfunction "DRVDD_17") (pintype "power_in"))
      (node (ref "IC200") (pin "60") (pinfunction "DVDD_60") (pintype "power_in"))
      (node (ref "IC200") (pin "64") (pinfunction "DRVDD_2_64") (pintype "power_in"))
      (node (ref "L143") (pin "2") (pinfunction "2_2") (pintype "passive"))
    )
    (net (code "15") (name "FPGA_ADIO00") (class "Default")
      (node (ref "IC200") (pin "12") (pinfunction "ADIO0/RX0_12") (pintype "passive"))
      (node (ref "IC400") (pin "83") (pinfunction "IO83_83") (pintype "bidirectional"))
    )
    (net (code "16") (name "FPGA_ADIO01") (class "Default")
      (node (ref "IC200") (pin "11") (pinfunction "ADIO1/RX1_11") (pintype "passive"))
      (node (ref "IC400") (pin "85") (pinfunction "IO85_85") (pintype "bidirectional"))
    )
    (net (code "17") (name "FPGA_ADIO02") (class "Default")
      (node (ref "IC200") (pin "10") (pinfunction "ADIO2/RX2_10") (pintype "passive"))
      (node (ref "IC400") (pin "86") (pinfunction "IO86_86") (pintype "bidirectional"))
    )
    (net (code "18") (name "FPGA_ADIO03") (class "Default")
      (node (ref "IC200") (pin "9") (pinfunction "ADIO3/RX3_9") (pintype "passive"))
      (node (ref "IC400") (pin "87") (pinfunction "IO87_87") (pintype "bidirectional"))
    )
    (net (code "19") (name "FPGA_ADIO04") (class "Default")
      (node (ref "IC200") (pin "8") (pinfunction "ADIO4/RX4_8") (pintype "passive"))
      (node (ref "IC400") (pin "98") (pinfunction "IO98_98") (pintype "bidirectional"))
    )
    (net (code "20") (name "FPGA_ADIO05") (class "Default")
      (node (ref "IC200") (pin "7") (pinfunction "ADIO5/RX5_7") (pintype "passive"))
      (node (ref "IC400") (pin "99") (pinfunction "IO99_99") (pintype "bidirectional"))
    )
    (net (code "21") (name "FPGA_ADIO06") (class "Default")
      (node (ref "IC200") (pin "6") (pinfunction "ADIO6/TX0_6") (pintype "passive"))
      (node (ref "IC400") (pin "100") (pinfunction "IO100_100") (pintype "bidirectional"))
    )
    (net (code "22") (name "FPGA_ADIO07") (class "Default")
      (node (ref "IC200") (pin "5") (pinfunction "ADIO7/TX1_5") (pintype "passive"))
      (node (ref "IC400") (pin "101") (pinfunction "IO101_101") (pintype "bidirectional"))
    )
    (net (code "23") (name "FPGA_ADIO08") (class "Default")
      (node (ref "IC200") (pin "4") (pinfunction "ADIO8/TX2_4") (pintype "passive"))
      (node (ref "IC400") (pin "103") (pinfunction "IO103_103") (pintype "bidirectional"))
    )
    (net (code "24") (name "FPGA_ADIO09") (class "Default")
      (node (ref "IC200") (pin "3") (pinfunction "ADIO9/TX3_3") (pintype "passive"))
      (node (ref "IC400") (pin "104") (pinfunction "IO104_104") (pintype "bidirectional"))
    )
    (net (code "25") (name "FPGA_ADIO10") (class "Default")
      (node (ref "IC200") (pin "2") (pinfunction "ADIO10/TX4_2") (pintype "passive"))
      (node (ref "IC400") (pin "105") (pinfunction "IO105_105") (pintype "bidirectional"))
    )
    (net (code "26") (name "FPGA_ADIO11") (class "Default")
      (node (ref "IC200") (pin "1") (pinfunction "ADIO11/TX5_1") (pintype "passive"))
      (node (ref "IC400") (pin "106") (pinfunction "IO106_106") (pintype "bidirectional"))
    )
    (net (code "27") (name "FPGA_CE0") (class "Default")
      (node (ref "IC400") (pin "137") (pinfunction "IO137_137") (pintype "bidirectional"))
    )
    (net (code "28") (name "FPGA_CE0_SPI0") (class "Default")
      (node (ref "IC400") (pin "43") (pinfunction "IO43_43") (pintype "bidirectional"))
      (node (ref "JP1") (pin "24") (pinfunction "24_24") (pintype "passive"))
    )
    (net (code "29") (name "FPGA_CE0_SPI1") (class "Default")
      (node (ref "IC400") (pin "50") (pinfunction "IO50_50") (pintype "bidirectional"))
      (node (ref "JP1") (pin "12") (pinfunction "12_12") (pintype "passive"))
    )
    (net (code "30") (name "FPGA_CE1_SPI0") (class "Default")
      (node (ref "IC400") (pin "42") (pinfunction "IO42_42") (pintype "bidirectional"))
      (node (ref "JP1") (pin "26") (pinfunction "26_26") (pintype "passive"))
    )
    (net (code "31") (name "FPGA_CE1_SPI1") (class "Default")
      (node (ref "IC400") (pin "51") (pinfunction "IO51_51") (pintype "bidirectional"))
      (node (ref "JP1") (pin "11") (pinfunction "11_11") (pintype "passive"))
    )
    (net (code "32") (name "FPGA_CE2_SPI1") (class "Default")
      (node (ref "IC400") (pin "33") (pinfunction "IO33_33") (pintype "bidirectional"))
      (node (ref "JP1") (pin "36") (pinfunction "36_36") (pintype "passive"))
    )
    (net (code "33") (name "FPGA_CLKOUT") (class "Default")
      (node (ref "IC200") (pin "19") (pinfunction "CLKOUT1_19") (pintype "passive"))
      (node (ref "IC400") (pin "72") (pinfunction "IO72_72") (pintype "bidirectional"))
    )
    (net (code "34") (name "FPGA_CLOCK") (class "Default")
      (node (ref "IC301") (pin "3") (pinfunction "CLK_3") (pintype "bidirectional"))
      (node (ref "IC400") (pin "25") (pinfunction "CLK3_25") (pintype "input"))
    )
    (net (code "35") (name "FPGA_CONF_DONE") (class "Default")
      (node (ref "IC400") (pin "92") (pinfunction "CONF_DONE_92") (pintype "input"))
      (node (ref "JP1") (pin "15") (pinfunction "15_15") (pintype "passive"))
      (node (ref "R404") (pin "1") (pinfunction "1_1") (pintype "passive"))
    )
    (net (code "36") (name "FPGA_DATA[0]") (class "Default")
      (node (ref "IC400") (pin "13") (pinfunction "IO13_13") (pintype "bidirectional"))
      (node (ref "JP1") (pin "33") (pinfunction "33_33") (pintype "passive"))
    )
    (net (code "37") (name "FPGA_DCLK") (class "Default")
      (node (ref "IC400") (pin "12") (pinfunction "DCLK_12") (pintype "input"))
      (node (ref "JP1") (pin "18") (pinfunction "18_18") (pintype "passive"))
    )
    (net (code "38") (name "FPGA_MISO_SPI0") (class "Default")
      (node (ref "IC400") (pin "46") (pinfunction "IO46_46") (pintype "bidirectional"))
      (node (ref "JP1") (pin "21") (pinfunction "21_21") (pintype "passive"))
    )
    (net (code "39") (name "FPGA_MISO_SPI1") (class "Default")
      (node (ref "IC400") (pin "39") (pinfunction "IO39_39") (pintype "bidirectional"))
      (node (ref "JP1") (pin "35") (pinfunction "35_35") (pintype "passive"))
    )
    (net (code "40") (name "FPGA_MODE") (class "Default")
      (node (ref "IC200") (pin "53") (pinfunction "MODE_53") (pintype "passive"))
      (node (ref "IC400") (pin "110") (pinfunction "IO110_110") (pintype "bidirectional"))
    )
    (net (code "41") (name "FPGA_MOSI_SPI0") (class "Default")
      (node (ref "IC400") (pin "49") (pinfunction "IO49_49") (pintype "bidirectional"))
      (node (ref "JP1") (pin "19") (pinfunction "19_19") (pintype "passive"))
    )
    (net (code "42") (name "FPGA_MOSI_SPI1") (class "Default")
      (node (ref "IC400") (pin "32") (pinfunction "IO32_32") (pintype "bidirectional"))
      (node (ref "JP1") (pin "38") (pinfunction "38_38") (pintype "passive"))
    )
    (net (code "43") (name "FPGA_NCONFIG") (class "Default")
      (node (ref "IC400") (pin "14") (pinfunction "NCONFIG_14") (pintype "input"))
      (node (ref "JP1") (pin "13") (pinfunction "13_13") (pintype "passive"))
    )
    (net (code "44") (name "FPGA_NSTATUS") (class "Default")
      (node (ref "IC400") (pin "9") (pinfunction "NSTATUS_9") (pintype "input"))
      (node (ref "JP1") (pin "37") (pinfunction "37_37") (pintype "passive"))
      (node (ref "R405") (pin "1") (pinfunction "1_1") (pintype "passive"))
    )
    (net (code "45") (name "FPGA_PGA0") (class "Default")
      (node (ref "IC200") (pin "29") (pinfunction "PGA0_29") (pintype "passive"))
      (node (ref "IC400") (pin "59") (pinfunction "IO59_59") (pintype "bidirectional"))
    )
    (net (code "46") (name "FPGA_PGA1") (class "Default")
      (node (ref "IC200") (pin "28") (pinfunction "PGA1_28") (pintype "passive"))
      (node (ref "IC400") (pin "60") (pinfunction "IO60_60") (pintype "bidirectional"))
    )
    (net (code "47") (name "FPGA_PGA2") (class "Default")
      (node (ref "IC200") (pin "27") (pinfunction "PGA2_27") (pintype "passive"))
      (node (ref "IC400") (pin "64") (pinfunction "IO64_64") (pintype "bidirectional"))
    )
    (net (code "48") (name "FPGA_PGA3") (class "Default")
      (node (ref "IC200") (pin "26") (pinfunction "PGA3_26") (pintype "passive"))
      (node (ref "IC400") (pin "65") (pinfunction "IO65_65") (pintype "bidirectional"))
    )
    (net (code "49") (name "FPGA_PGA4") (class "Default")
      (node (ref "IC200") (pin "25") (pinfunction "PGA4_25") (pintype "passive"))
      (node (ref "IC400") (pin "66") (pinfunction "IO66_66") (pintype "bidirectional"))
    )
    (net (code "50") (name "FPGA_PGA5") (class "Default")
      (node (ref "IC200") (pin "24") (pinfunction "GAIN/PGA5_24") (pintype "passive"))
      (node (ref "IC400") (pin "67") (pinfunction "IO67_67") (pintype "bidirectional"))
    )
    (net (code "51") (name "FPGA_RESET") (class "Default")
      (node (ref "IC200") (pin "30") (pinfunction "RESET_30") (pintype "passive"))
      (node (ref "IC400") (pin "58") (pinfunction "IO58_58") (pintype "bidirectional"))
    )
    (net (code "52") (name "FPGA_RXCLK") (class "Default")
      (node (ref "IC200") (pin "16") (pinfunction "RXCLK_16") (pintype "passive"))
      (node (ref "IC400") (pin "76") (pinfunction "IO76_76") (pintype "bidirectional"))
    )
    (net (code "53") (name "FPGA_RXEN") (class "Default")
      (node (ref "IC200") (pin "13") (pinfunction "RXEN/RXSYNC_13") (pintype "passive"))
      (node (ref "IC400") (pin "80") (pinfunction "IO80_80") (pintype "bidirectional"))
    )
    (net (code "54") (name "FPGA_SCLK") (class "Default")
      (node (ref "IC200") (pin "22") (pinfunction "SCLK_22") (pintype "passive"))
      (node (ref "IC400") (pin "68") (pinfunction "IO68_68") (pintype "bidirectional"))
    )
    (net (code "55") (name "FPGA_SCLK_SPI0") (class "Default")
      (node (ref "IC400") (pin "44") (pinfunction "IO44_44") (pintype "bidirectional"))
      (node (ref "JP1") (pin "23") (pinfunction "23_23") (pintype "passive"))
    )
    (net (code "56") (name "FPGA_SCLK_SPI1") (class "Default")
      (node (ref "IC400") (pin "31") (pinfunction "IO31_31") (pintype "bidirectional"))
      (node (ref "JP1") (pin "40") (pinfunction "40_40") (pintype "passive"))
    )
    (net (code "57") (name "FPGA_SDIO") (class "Default")
      (node (ref "IC200") (pin "20") (pinfunction "SDIO_20") (pintype "passive"))
      (node (ref "IC400") (pin "71") (pinfunction "IO71_71") (pintype "bidirectional"))
    )
    (net (code "58") (name "FPGA_SDO") (class "Default")
      (node (ref "IC200") (pin "21") (pinfunction "SDO_21") (pintype "passive"))
      (node (ref "IC400") (pin "69") (pinfunction "IO69_69") (pintype "bidirectional"))
    )
    (net (code "59") (name "FPGA_SEN") (class "Default")
      (node (ref "IC200") (pin "23") (pinfunction "SEN_23") (pintype "passive"))
      (node (ref "IC400") (pin "7") (pinfunction "IO7_7") (pintype "output"))
    )
    (net (code "60") (name "FPGA_TXCLK") (class "Default")
      (node (ref "IC200") (pin "15") (pinfunction "TXCLK/TXQUIET_15") (pintype "passive"))
      (node (ref "IC400") (pin "77") (pinfunction "IO77_77") (pintype "bidirectional"))
    )
    (net (code "61") (name "FPGA_TXEN") (class "Default")
      (node (ref "IC200") (pin "14") (pinfunction "TXEN/TXSYNC_14") (pintype "passive"))
      (node (ref "IC400") (pin "79") (pinfunction "IO79_79") (pintype "bidirectional"))
    )
    (net (code "62") (name "GND") (class "Default")
      (node (ref "C100") (pin "1") (pinfunction "1_1") (pintype "passive"))
      (node (ref "C101") (pin "1") (pinfunction "1_1") (pintype "passive"))
      (node (ref "C102") (pin "-") (pinfunction "-_-") (pintype "passive"))
      (node (ref "C110") (pin "1") (pinfunction "1_1") (pintype "passive"))
      (node (ref "C111") (pin "1") (pinfunction "1_1") (pintype "passive"))
      (node (ref "C112") (pin "-") (pinfunction "-_-") (pintype "passive"))
      (node (ref "C113") (pin "1") (pinfunction "1_1") (pintype "passive"))
      (node (ref "C114") (pin "1") (pinfunction "1_1") (pintype "passive"))
      (node (ref "C115") (pin "1") (pinfunction "1_1") (pintype "passive"))
      (node (ref "C116") (pin "1") (pinfunction "1_1") (pintype "passive"))
      (node (ref "C120") (pin "1") (pinfunction "1_1") (pintype "passive"))
      (node (ref "C121") (pin "1") (pinfunction "1_1") (pintype "passive"))
      (node (ref "C122") (pin "-") (pinfunction "-_-") (pintype "passive"))
      (node (ref "C123") (pin "1") (pinfunction "1_1") (pintype "passive"))
      (node (ref "C124") (pin "1") (pinfunction "1_1") (pintype "passive"))
      (node (ref "C125") (pin "1") (pinfunction "1_1") (pintype "passive"))
      (node (ref "C126") (pin "1") (pinfunction "1_1") (pintype "passive"))
      (node (ref "C127") (pin "1") (pinfunction "1_1") (pintype "passive"))
      (node (ref "C128") (pin "1") (pinfunction "1_1") (pintype "passive"))
      (node (ref "C129") (pin "1") (pinfunction "1_1") (pintype "passive"))
      (node (ref "C130") (pin "1") (pinfunction "1_1") (pintype "passive"))
      (node (ref "C131") (pin "1") (pinfunction "1_1") (pintype "passive"))
      (node (ref "C132") (pin "1") (pinfunction "1_1") (pintype "passive"))
      (node (ref "C133") (pin "1") (pinfunction "1_1") (pintype "passive"))
      (node (ref "C134") (pin "1") (pinfunction "1_1") (pintype "passive"))
      (node (ref "C140") (pin "1") (pinfunction "1_1") (pintype "passive"))
      (node (ref "C141") (pin "1") (pinfunction "1_1") (pintype "passive"))
      (node (ref "C142") (pin "-") (pinfunction "-_-") (pintype "passive"))
      (node (ref "C143") (pin "1") (pinfunction "1_1") (pintype "passive"))
      (node (ref "C144") (pin "1") (pinfunction "1_1") (pintype "passive"))
      (node (ref "C145") (pin "-") (pinfunction "-_-") (pintype "passive"))
      (node (ref "C146") (pin "1") (pinfunction "1_1") (pintype "passive"))
      (node (ref "C147") (pin "1") (pinfunction "1_1") (pintype "passive"))
      (node (ref "C148") (pin "1") (pinfunction "1_1") (pintype "passive"))
      (node (ref "C149") (pin "-") (pinfunction "-_-") (pintype "passive"))
      (node (ref "C150") (pin "1") (pinfunction "1_1") (pintype "passive"))
      (node (ref "C151") (pin "1") (pinfunction "1_1") (pintype "passive"))
      (node (ref "C152") (pin "-") (pinfunction "-_-") (pintype "passive"))
      (node (ref "C160") (pin "1") (pinfunction "1_1") (pintype "passive"))
      (node (ref "C161") (pin "1") (pinfunction "1_1") (pintype "passive"))
      (node (ref "C162") (pin "-") (pinfunction "-_-") (pintype "passive"))
      (node (ref "C163") (pin "1") (pinfunction "1_1") (pintype "passive"))
      (node (ref "C164") (pin "1") (pinfunction "1_1") (pintype "passive"))
      (node (ref "C165") (pin "1") (pinfunction "1_1") (pintype "passive"))
      (node (ref "C166") (pin "1") (pinfunction "1_1") (pintype "passive"))
      (node (ref "C167") (pin "1") (pinfunction "1_1") (pintype "passive"))
      (node (ref "C168") (pin "1") (pinfunction "1_1") (pintype "passive"))
      (node (ref "C169") (pin "1") (pinfunction "1_1") (pintype "passive"))
      (node (ref "C170") (pin "1") (pinfunction "1_1") (pintype "passive"))
      (node (ref "C201") (pin "1") (pinfunction "1_1") (pintype "passive"))
      (node (ref "C204") (pin "1") (pinfunction "1_1") (pintype "passive"))
      (node (ref "C207") (pin "1") (pinfunction "1_1") (pintype "passive"))
      (node (ref "C208") (pin "1") (pinfunction "1_1") (pintype "passive"))
      (node (ref "C211") (pin "1") (pinfunction "1_1") (pintype "passive"))
      (node (ref "C301") (pin "1") (pinfunction "1_1") (pintype "passive"))
      (node (ref "D1") (pin "B") (pinfunction "B_B") (pintype "bidirectional"))
      (node (ref "F200") (pin "2@1") (pinfunction "2_2@1") (pintype "passive"))
      (node (ref "F200") (pin "2@2") (pinfunction "2_2@2") (pintype "passive"))
      (node (ref "F201") (pin "2@1") (pinfunction "2_2@1") (pintype "passive"))
      (node (ref "F201") (pin "2@2") (pinfunction "2_2@2") (pintype "passive"))
      (node (ref "F202") (pin "2@1") (pinfunction "2_2@1") (pintype "passive"))
      (node (ref "F202") (pin "2@2") (pinfunction "2_2@2") (pintype "passive"))
      (node (ref "F203") (pin "2@1") (pinfunction "2_2@1") (pintype "passive"))
      (node (ref "F203") (pin "2@2") (pinfunction "2_2@2") (pintype "passive"))
      (node (ref "IC100") (pin "1") (pinfunction "ADJ_1") (pintype "input"))
      (node (ref "IC101") (pin "1") (pinfunction "ADJ_1") (pintype "input"))
      (node (ref "IC102") (pin "1") (pinfunction "ADJ_1") (pintype "input"))
      (node (ref "IC103") (pin "1") (pinfunction "ADJ_1") (pintype "input"))
      (node (ref "IC200") (pin "18") (pinfunction "DRVSS_18") (pintype "passive"))
      (node (ref "IC200") (pin "31") (pinfunction "AVSS_31") (pintype "passive"))
      (node (ref "IC200") (pin "34") (pinfunction "AVSS_2_34") (pintype "passive"))
      (node (ref "IC200") (pin "36") (pinfunction "AVSS_3_36") (pintype "passive"))
      (node (ref "IC200") (pin "39") (pinfunction "AVSS_4_39") (pintype "passive"))
      (node (ref "IC200") (pin "44") (pinfunction "AVSS_5_44") (pintype "passive"))
      (node (ref "IC200") (pin "47") (pinfunction "AVSS_6_47") (pintype "passive"))
      (node (ref "IC200") (pin "48") (pinfunction "AVSS_7_48") (pintype "passive"))
      (node (ref "IC200") (pin "54") (pinfunction "CONFIG_54") (pintype "passive"))
      (node (ref "IC200") (pin "55") (pinfunction "CLKVSS_55") (pintype "passive"))
      (node (ref "IC200") (pin "59") (pinfunction "DVSS_59") (pintype "passive"))
      (node (ref "IC200") (pin "62") (pinfunction "PWR_DWN_62") (pintype "passive"))
      (node (ref "IC200") (pin "63") (pinfunction "DRVSS_2_63") (pintype "passive"))
      (node (ref "IC200") (pin "65") (pinfunction "EP_65") (pintype "passive"))
      (node (ref "IC300") (pin "3") (pinfunction "GND_3") (pintype "power_in"))
      (node (ref "IC301") (pin "2") (pinfunction "GND_2") (pintype "power_in"))
      (node (ref "IC400") (pin "108") (pinfunction "GND_108") (pintype "power_in"))
      (node (ref "IC400") (pin "118") (pinfunction "GND_118") (pintype "power_in"))
      (node (ref "IC400") (pin "123") (pinfunction "GND_123") (pintype "power_in"))
      (node (ref "IC400") (pin "131") (pinfunction "GND_131") (pintype "power_in"))
      (node (ref "IC400") (pin "140") (pinfunction "GND_140") (pintype "power_in"))
      (node (ref "IC400") (pin "19") (pinfunction "GND_19") (pintype "power_in"))
      (node (ref "IC400") (pin "2") (pinfunction "GND_2") (pintype "power_in"))
      (node (ref "IC400") (pin "21") (pinfunction "NCE_21") (pintype "input"))
      (node (ref "IC400") (pin "27") (pinfunction "GND_27") (pintype "power_in"))
      (node (ref "IC400") (pin "36") (pinfunction "GND_36") (pintype "power_in"))
      (node (ref "IC400") (pin "41") (pinfunction "GND_41") (pintype "power_in"))
      (node (ref "IC400") (pin "48") (pinfunction "GND_48") (pintype "power_in"))
      (node (ref "IC400") (pin "57") (pinfunction "GND_57") (pintype "power_in"))
      (node (ref "IC400") (pin "63") (pinfunction "GND_63") (pintype "power_in"))
      (node (ref "IC400") (pin "74") (pinfunction "GND_74") (pintype "power_in"))
      (node (ref "IC400") (pin "82") (pinfunction "GND_82") (pintype "power_in"))
      (node (ref "IC400") (pin "94") (pinfunction "MSEL0_94") (pintype "input"))
      (node (ref "IC400") (pin "95") (pinfunction "GND_95") (pintype "power_in"))
      (node (ref "IC400") (pin "96") (pinfunction "MSEL1_96") (pintype "input"))
      (node (ref "IC400") (pin "97") (pinfunction "MSEL2_97") (pintype "input"))
      (node (ref "IC400") (pin "E") (pinfunction "GND_E") (pintype "power_in"))
      (node (ref "JP1") (pin "14") (pinfunction "14_14") (pintype "passive"))
      (node (ref "JP1") (pin "20") (pinfunction "20_20") (pintype "passive"))
      (node (ref "JP1") (pin "25") (pinfunction "25_25") (pintype "passive"))
      (node (ref "JP1") (pin "30") (pinfunction "30_30") (pintype "passive"))
      (node (ref "JP1") (pin "34") (pinfunction "34_34") (pintype "passive"))
      (node (ref "JP1") (pin "39") (pinfunction "39_39") (pintype "passive"))
      (node (ref "JP1") (pin "6") (pinfunction "6_6") (pintype "passive"))
      (node (ref "JP1") (pin "9") (pinfunction "9_9") (pintype "passive"))
      (node (ref "JP2") (pin "19") (pinfunction "19_19") (pintype "passive"))
      (node (ref "JP2") (pin "20") (pinfunction "20_20") (pintype "passive"))
      (node (ref "LED2V5") (pin "C") (pinfunction "C_C") (pintype "passive"))
      (node (ref "LED3V3A") (pin "C") (pinfunction "C_C") (pintype "passive"))
      (node (ref "LED3V3B") (pin "C") (pinfunction "C_C") (pintype "passive"))
      (node (ref "LED801") (pin "C") (pinfunction "C_C") (pintype "passive"))
      (node (ref "LED802") (pin "C") (pinfunction "C_C") (pintype "passive"))
      (node (ref "LED803") (pin "C") (pinfunction "C_C") (pintype "passive"))
      (node (ref "LED804") (pin "C") (pinfunction "C_C") (pintype "passive"))
      (node (ref "R100") (pin "1") (pinfunction "1_1") (pintype "passive"))
      (node (ref "R201") (pin "2") (pinfunction "2_2") (pintype "passive"))
      (node (ref "T201") (pin "1") (pinfunction "P2_1") (pintype "passive"))
      (node (ref "T202") (pin "3") (pinfunction "P1_3") (pintype "passive"))
      (node (ref "X201") (pin "2") (pinfunction "2_2") (pintype "passive"))
      (node (ref "X201") (pin "3") (pinfunction "2_3") (pintype "passive"))
      (node (ref "X201") (pin "4") (pinfunction "2_4") (pintype "passive"))
      (node (ref "X201") (pin "5") (pinfunction "2_5") (pintype "passive"))
      (node (ref "X202") (pin "2") (pinfunction "2_2") (pintype "passive"))
      (node (ref "X202") (pin "3") (pinfunction "2_3") (pintype "passive"))
      (node (ref "X202") (pin "4") (pinfunction "2_4") (pintype "passive"))
      (node (ref "X202") (pin "5") (pinfunction "2_5") (pintype "passive"))
    )
    (net (code "63") (name "IO-01") (class "Default")
      (node (ref "IC400") (pin "144") (pinfunction "IO144_144") (pintype "bidirectional"))
      (node (ref "JP2") (pin "3") (pinfunction "3_3") (pintype "passive"))
    )
    (net (code "64") (name "IO-02") (class "Default")
      (node (ref "IC400") (pin "143") (pinfunction "IO143_143") (pintype "bidirectional"))
      (node (ref "JP2") (pin "4") (pinfunction "4_4") (pintype "passive"))
    )
    (net (code "65") (name "IO-03") (class "Default")
      (node (ref "IC400") (pin "142") (pinfunction "IO142_142") (pintype "bidirectional"))
      (node (ref "JP2") (pin "5") (pinfunction "5_5") (pintype "passive"))
    )
    (net (code "66") (name "IO-04") (class "Default")
      (node (ref "IC400") (pin "141") (pinfunction "IO141_141") (pintype "bidirectional"))
      (node (ref "JP2") (pin "6") (pinfunction "6_6") (pintype "passive"))
    )
    (net (code "67") (name "IO-05") (class "Default")
      (node (ref "IC400") (pin "136") (pinfunction "IO136_136") (pintype "bidirectional"))
      (node (ref "JP2") (pin "7") (pinfunction "7_7") (pintype "passive"))
    )
    (net (code "68") (name "IO-06") (class "Default")
      (node (ref "IC400") (pin "135") (pinfunction "IO135_135") (pintype "bidirectional"))
      (node (ref "JP2") (pin "8") (pinfunction "8_8") (pintype "passive"))
    )
    (net (code "69") (name "IO-07") (class "Default")
      (node (ref "IC400") (pin "133") (pinfunction "IO133_133") (pintype "bidirectional"))
      (node (ref "JP2") (pin "9") (pinfunction "9_9") (pintype "passive"))
    )
    (net (code "70") (name "IO-08") (class "Default")
      (node (ref "IC400") (pin "132") (pinfunction "IO132_132") (pintype "bidirectional"))
      (node (ref "JP2") (pin "10") (pinfunction "10_10") (pintype "passive"))
    )
    (net (code "71") (name "IO-09") (class "Default")
      (node (ref "IC400") (pin "125") (pinfunction "IO125_125") (pintype "bidirectional"))
      (node (ref "JP2") (pin "11") (pinfunction "11_11") (pintype "passive"))
    )
    (net (code "72") (name "IO-10") (class "Default")
      (node (ref "IC400") (pin "121") (pinfunction "IO121_121") (pintype "bidirectional"))
      (node (ref "JP2") (pin "12") (pinfunction "12_12") (pintype "passive"))
    )
    (net (code "73") (name "IO-11") (class "Default")
      (node (ref "IC400") (pin "120") (pinfunction "IO120_120") (pintype "bidirectional"))
      (node (ref "JP2") (pin "13") (pinfunction "13_13") (pintype "passive"))
    )
    (net (code "74") (name "IO-12") (class "Default")
      (node (ref "IC400") (pin "119") (pinfunction "IO119_119") (pintype "bidirectional"))
      (node (ref "JP2") (pin "14") (pinfunction "14_14") (pintype "passive"))
    )
    (net (code "75") (name "IO-13") (class "Default")
      (node (ref "IC400") (pin "115") (pinfunction "IO115_115") (pintype "bidirectional"))
      (node (ref "JP2") (pin "15") (pinfunction "15_15") (pintype "passive"))
    )
    (net (code "76") (name "IO-14") (class "Default")
      (node (ref "IC400") (pin "114") (pinfunction "IO114_114") (pintype "bidirectional"))
      (node (ref "JP2") (pin "16") (pinfunction "16_16") (pintype "passive"))
    )
    (net (code "77") (name "IO-15") (class "Default")
      (node (ref "IC400") (pin "113") (pinfunction "IO113_113") (pintype "bidirectional"))
      (node (ref "JP2") (pin "17") (pinfunction "17_17") (pintype "passive"))
    )
    (net (code "78") (name "IO-16") (class "Default")
      (node (ref "IC400") (pin "112") (pinfunction "IO112_112") (pintype "bidirectional"))
      (node (ref "JP2") (pin "18") (pinfunction "18_18") (pintype "passive"))
    )
    (net (code "79") (name "Net-(C200-Pad1)") (class "Default")
      (node (ref "C200") (pin "1") (pinfunction "1_1") (pintype "passive"))
      (node (ref "F200") (pin "1") (pinfunction "1_1") (pintype "passive"))
    )
    (net (code "80") (name "Net-(C200-Pad2)") (class "Default")
      (node (ref "C200") (pin "2") (pinfunction "2_2") (pintype "passive"))
      (node (ref "X201") (pin "1") (pinfunction "1_1") (pintype "passive"))
    )
    (net (code "81") (name "Net-(C202-Pad1)") (class "Default")
      (node (ref "C202") (pin "1") (pinfunction "1_1") (pintype "passive"))
      (node (ref "C203") (pin "2") (pinfunction "2_2") (pintype "passive"))
      (node (ref "D1") (pin "A") (pinfunction "A_A") (pintype "bidirectional"))
    )
    (net (code "82") (name "Net-(C202-Pad2)") (class "Default")
      (node (ref "C202") (pin "2") (pinfunction "2_2") (pintype "passive"))
      (node (ref "X202") (pin "1") (pinfunction "1_1") (pintype "passive"))
    )
    (net (code "83") (name "Net-(C203-Pad1)") (class "Default")
      (node (ref "C203") (pin "1") (pinfunction "1_1") (pintype "passive"))
      (node (ref "F202") (pin "1") (pinfunction "1_1") (pintype "passive"))
    )
    (net (code "84") (name "Net-(F200-Pad3)") (class "Default")
      (node (ref "F200") (pin "3") (pinfunction "3_3") (pintype "passive"))
      (node (ref "F201") (pin "1") (pinfunction "1_1") (pintype "passive"))
    )
    (net (code "85") (name "Net-(F202-Pad3)") (class "Default")
      (node (ref "F202") (pin "3") (pinfunction "3_3") (pintype "passive"))
      (node (ref "F203") (pin "1") (pinfunction "1_1") (pintype "passive"))
    )
    (net (code "86") (name "Net-(IC200-IOUT_N+)") (class "Default")
      (node (ref "IC200") (pin "50") (pinfunction "IOUT_N+_50") (pintype "passive"))
      (node (ref "T201") (pin "4") (pinfunction "S1_4") (pintype "passive"))
    )
    (net (code "87") (name "Net-(IC200-IOUT_N-)") (class "Default")
      (node (ref "IC200") (pin "46") (pinfunction "IOUT_N-_46") (pintype "passive"))
      (node (ref "T201") (pin "6") (pinfunction "S2_6") (pintype "passive"))
    )
    (net (code "88") (name "Net-(IC200-OSCIN)") (class "Default")
      (node (ref "IC200") (pin "57") (pinfunction "OSCIN_57") (pintype "passive"))
      (node (ref "IC300") (pin "4") (pinfunction "CLK+_4") (pintype "output"))
    )
    (net (code "89") (name "Net-(IC200-REFADJ)") (class "Default")
      (node (ref "IC200") (pin "41") (pinfunction "REFADJ_41") (pintype "passive"))
      (node (ref "R201") (pin "1") (pinfunction "1_1") (pintype "passive"))
    )
    (net (code "90") (name "Net-(IC200-REFB)") (class "Default")
      (node (ref "C208") (pin "2") (pinfunction "2_2") (pintype "passive"))
      (node (ref "C209") (pin "1") (pinfunction "1_1") (pintype "passive"))
      (node (ref "C210") (pin "1") (pinfunction "1_1") (pintype "passive"))
      (node (ref "IC200") (pin "32") (pinfunction "REFB_32") (pintype "passive"))
    )
    (net (code "91") (name "Net-(IC200-REFIO)") (class "Default")
      (node (ref "C211") (pin "2") (pinfunction "2_2") (pintype "passive"))
      (node (ref "IC200") (pin "42") (pinfunction "REFIO_42") (pintype "passive"))
    )
    (net (code "92") (name "Net-(IC200-REFT)") (class "Default")
      (node (ref "C207") (pin "2") (pinfunction "2_2") (pintype "passive"))
      (node (ref "C209") (pin "2") (pinfunction "2_2") (pintype "passive"))
      (node (ref "C210") (pin "2") (pinfunction "2_2") (pintype "passive"))
      (node (ref "IC200") (pin "33") (pinfunction "REFT_33") (pintype "passive"))
    )
    (net (code "93") (name "Net-(IC200-RX+)") (class "Default")
      (node (ref "C205") (pin "1") (pinfunction "1_1") (pintype "passive"))
      (node (ref "IC200") (pin "38") (pinfunction "RX+_38") (pintype "passive"))
    )
    (net (code "94") (name "Net-(IC200-RX-)") (class "Default")
      (node (ref "C206") (pin "1") (pinfunction "1_1") (pintype "passive"))
      (node (ref "IC200") (pin "37") (pinfunction "RX-_37") (pintype "passive"))
    )
    (net (code "95") (name "Net-(L1-Pad2)") (class "Default")
      (node (ref "L1") (pin "2") (pinfunction "2_2") (pintype "passive"))
      (node (ref "R202") (pin "1") (pinfunction "1_1") (pintype "passive"))
      (node (ref "R203") (pin "1") (pinfunction "1_1") (pintype "passive"))
    )
    (net (code "96") (name "Net-(LED2V5-PadA)") (class "Default")
      (node (ref "LED2V5") (pin "A") (pinfunction "A_A") (pintype "passive"))
      (node (ref "R103") (pin "1") (pinfunction "1_1") (pintype "passive"))
    )
    (net (code "97") (name "Net-(LED3V3A-PadA)") (class "Default")
      (node (ref "LED3V3A") (pin "A") (pinfunction "A_A") (pintype "passive"))
      (node (ref "R101") (pin "1") (pinfunction "1_1") (pintype "passive"))
    )
    (net (code "98") (name "Net-(LED3V3B-PadA)") (class "Default")
      (node (ref "LED3V3B") (pin "A") (pinfunction "A_A") (pintype "passive"))
      (node (ref "R102") (pin "1") (pinfunction "1_1") (pintype "passive"))
    )
    (net (code "99") (name "Net-(LED801-PadA)") (class "Default")
      (node (ref "LED801") (pin "A") (pinfunction "A_A") (pintype "passive"))
      (node (ref "R800") (pin "1") (pinfunction "1_1") (pintype "passive"))
    )
    (net (code "100") (name "Net-(LED802-PadA)") (class "Default")
      (node (ref "LED802") (pin "A") (pinfunction "A_A") (pintype "passive"))
      (node (ref "R801") (pin "1") (pinfunction "1_1") (pintype "passive"))
    )
    (net (code "101") (name "Net-(LED803-PadA)") (class "Default")
      (node (ref "LED803") (pin "A") (pinfunction "A_A") (pintype "passive"))
      (node (ref "R802") (pin "1") (pinfunction "1_1") (pintype "passive"))
    )
    (net (code "102") (name "Net-(LED804-PadA)") (class "Default")
      (node (ref "LED804") (pin "A") (pinfunction "A_A") (pintype "passive"))
      (node (ref "R803") (pin "1") (pinfunction "1_1") (pintype "passive"))
    )
    (net (code "103") (name "Net-(T201-P1)") (class "Default")
      (node (ref "F201") (pin "3") (pinfunction "3_3") (pintype "passive"))
      (node (ref "T201") (pin "3") (pinfunction "P1_3") (pintype "passive"))
    )
    (net (code "104") (name "Net-(T201-ST)") (class "Default")
      (node (ref "C201") (pin "2") (pinfunction "2_2") (pintype "passive"))
      (node (ref "L1") (pin "1") (pinfunction "1_1") (pintype "passive"))
      (node (ref "T201") (pin "5") (pinfunction "ST_5") (pintype "passive"))
    )
    (net (code "105") (name "Net-(T202-P2)") (class "Default")
      (node (ref "F203") (pin "3") (pinfunction "3_3") (pintype "passive"))
      (node (ref "T202") (pin "1") (pinfunction "P2_1") (pintype "passive"))
    )
    (net (code "106") (name "Net-(T202-S1)") (class "Default")
      (node (ref "C205") (pin "2") (pinfunction "2_2") (pintype "passive"))
      (node (ref "T202") (pin "4") (pinfunction "S1_4") (pintype "passive"))
    )
    (net (code "107") (name "Net-(T202-S2)") (class "Default")
      (node (ref "C206") (pin "2") (pinfunction "2_2") (pintype "passive"))
      (node (ref "T202") (pin "6") (pinfunction "S2_6") (pintype "passive"))
    )
    (net (code "108") (name "Net-(T202-ST)") (class "Default")
      (node (ref "C204") (pin "2") (pinfunction "2_2") (pintype "passive"))
      (node (ref "T202") (pin "5") (pinfunction "ST_5") (pintype "passive"))
    )
    (net (code "109") (name "SCL") (class "Default")
      (node (ref "IC300") (pin "8") (pinfunction "SCL_8") (pintype "input"))
      (node (ref "JP1") (pin "5") (pinfunction "5_5") (pintype "passive"))
      (node (ref "R301") (pin "1") (pinfunction "1_1") (pintype "passive"))
    )
    (net (code "110") (name "SDA") (class "Default")
      (node (ref "IC300") (pin "7") (pinfunction "SDA_7") (pintype "input"))
      (node (ref "JP1") (pin "3") (pinfunction "3_3") (pintype "passive"))
      (node (ref "R302") (pin "1") (pinfunction "1_1") (pintype "passive"))
    )
    (net (code "111") (name "SI570_OE") (class "Default")
      (node (ref "IC300") (pin "2") (pinfunction "OE_2") (pintype "input"))
      (node (ref "IC400") (pin "111") (pinfunction "IO111_111") (pintype "bidirectional"))
    )
    (net (code "112") (name "unconnected-(IC200-CLKOUT2-Pad61)") (class "Default")
      (node (ref "IC200") (pin "61") (pinfunction "CLKOUT2_61") (pintype "passive"))
    )
    (net (code "113") (name "unconnected-(IC200-IOUT_G+-Pad49)") (class "Default")
      (node (ref "IC200") (pin "49") (pinfunction "IOUT_G+_49") (pintype "passive"))
    )
    (net (code "114") (name "unconnected-(IC200-IOUT_G--Pad45)") (class "Default")
      (node (ref "IC200") (pin "45") (pinfunction "IOUT_G-_45") (pintype "passive"))
    )
    (net (code "115") (name "unconnected-(IC200-IOUT_P+-Pad52)") (class "Default")
      (node (ref "IC200") (pin "52") (pinfunction "IOUT_P+_52") (pintype "passive"))
    )
    (net (code "116") (name "unconnected-(IC200-IOUT_P--Pad51)") (class "Default")
      (node (ref "IC200") (pin "51") (pinfunction "IOUT_P-_51") (pintype "passive"))
    )
    (net (code "117") (name "unconnected-(IC200-XTAL-Pad56)") (class "Default")
      (node (ref "IC200") (pin "56") (pinfunction "XTAL_56") (pintype "passive"))
    )
    (net (code "118") (name "unconnected-(IC300-CLK--Pad5)") (class "Default")
      (node (ref "IC300") (pin "5") (pinfunction "CLK-_5") (pintype "output"))
    )
    (net (code "119") (name "unconnected-(IC400-CLK0-Pad22)") (class "Default")
      (node (ref "IC400") (pin "22") (pinfunction "CLK0_22") (pintype "input"))
    )
    (net (code "120") (name "unconnected-(IC400-CLK1-Pad23)") (class "Default")
      (node (ref "IC400") (pin "23") (pinfunction "CLK1_23") (pintype "input"))
    )
    (net (code "121") (name "unconnected-(IC400-CLK2-Pad24)") (class "Default")
      (node (ref "IC400") (pin "24") (pinfunction "CLK2_24") (pintype "input"))
    )
    (net (code "122") (name "unconnected-(IC400-CLK4-Pad91)") (class "Default")
      (node (ref "IC400") (pin "91") (pinfunction "CLK4_91") (pintype "input"))
    )
    (net (code "123") (name "unconnected-(IC400-CLK5-Pad90)") (class "Default")
      (node (ref "IC400") (pin "90") (pinfunction "CLK5_90") (pintype "input"))
    )
    (net (code "124") (name "unconnected-(IC400-CLK6-Pad89)") (class "Default")
      (node (ref "IC400") (pin "89") (pinfunction "CLK6_89") (pintype "input"))
    )
    (net (code "125") (name "unconnected-(IC400-CLK7-Pad88)") (class "Default")
      (node (ref "IC400") (pin "88") (pinfunction "CLK7_88") (pintype "input"))
    )
    (net (code "126") (name "unconnected-(IC400-CLK8-Pad126)") (class "Default")
      (node (ref "IC400") (pin "126") (pinfunction "CLK8_126") (pintype "input"))
    )
    (net (code "127") (name "unconnected-(IC400-CLK9-Pad127)") (class "Default")
      (node (ref "IC400") (pin "127") (pinfunction "CLK9_127") (pintype "input"))
    )
    (net (code "128") (name "unconnected-(IC400-CLK10-Pad128)") (class "Default")
      (node (ref "IC400") (pin "128") (pinfunction "CLK10_128") (pintype "input"))
    )
    (net (code "129") (name "unconnected-(IC400-CLK11-Pad129)") (class "Default")
      (node (ref "IC400") (pin "129") (pinfunction "CLK11_129") (pintype "input"))
    )
    (net (code "130") (name "unconnected-(IC400-CLK12-Pad55)") (class "Default")
      (node (ref "IC400") (pin "55") (pinfunction "CLK12_55") (pintype "input"))
    )
    (net (code "131") (name "unconnected-(IC400-CLK13-Pad54)") (class "Default")
      (node (ref "IC400") (pin "54") (pinfunction "CLK13_54") (pintype "input"))
    )
    (net (code "132") (name "unconnected-(IC400-CLK14-Pad53)") (class "Default")
      (node (ref "IC400") (pin "53") (pinfunction "CLK14_53") (pintype "input"))
    )
    (net (code "133") (name "unconnected-(IC400-CLK15-Pad52)") (class "Default")
      (node (ref "IC400") (pin "52") (pinfunction "CLK15_52") (pintype "input"))
    )
    (net (code "134") (name "unconnected-(IC400-IO8-Pad8)") (class "Default")
      (node (ref "IC400") (pin "8") (pinfunction "IO8_8") (pintype "output"))
    )
    (net (code "135") (name "unconnected-(IC400-IO10-Pad10)") (class "Default")
      (node (ref "IC400") (pin "10") (pinfunction "IO10_10") (pintype "bidirectional"))
    )
    (net (code "136") (name "unconnected-(IC400-IO11-Pad11)") (class "Default")
      (node (ref "IC400") (pin "11") (pinfunction "IO11_11") (pintype "bidirectional"))
    )
    (net (code "137") (name "unconnected-(IC400-TCK-Pad16)") (class "Default")
      (node (ref "IC400") (pin "16") (pinfunction "TCK_16") (pintype "input"))
    )
    (net (code "138") (name "unconnected-(IC400-TDI-Pad15)") (class "Default")
      (node (ref "IC400") (pin "15") (pinfunction "TDI_15") (pintype "input"))
    )
    (net (code "139") (name "unconnected-(IC400-TDO-Pad20)") (class "Default")
      (node (ref "IC400") (pin "20") (pinfunction "TDO_20") (pintype "output"))
    )
    (net (code "140") (name "unconnected-(IC400-TMS-Pad18)") (class "Default")
      (node (ref "IC400") (pin "18") (pinfunction "TMS_18") (pintype "input"))
    )
    (net (code "141") (name "unconnected-(JP1-Pad7)") (class "Default")
      (node (ref "JP1") (pin "7") (pinfunction "7_7") (pintype "passive"))
    )
    (net (code "142") (name "unconnected-(JP1-Pad8)") (class "Default")
      (node (ref "JP1") (pin "8") (pinfunction "8_8") (pintype "passive"))
    )
    (net (code "143") (name "unconnected-(JP1-Pad10)") (class "Default")
      (node (ref "JP1") (pin "10") (pinfunction "10_10") (pintype "passive"))
    )
    (net (code "144") (name "unconnected-(JP1-Pad16)") (class "Default")
      (node (ref "JP1") (pin "16") (pinfunction "16_16") (pintype "passive"))
    )
    (net (code "145") (name "unconnected-(JP1-Pad17)") (class "Default")
      (node (ref "JP1") (pin "17") (pinfunction "17_17") (pintype "passive"))
    )
    (net (code "146") (name "unconnected-(JP1-Pad22)") (class "Default")
      (node (ref "JP1") (pin "22") (pinfunction "22_22") (pintype "passive"))
    )
    (net (code "147") (name "unconnected-(JP1-Pad27)") (class "Default")
      (node (ref "JP1") (pin "27") (pinfunction "27_27") (pintype "passive"))
    )
    (net (code "148") (name "unconnected-(JP1-Pad28)") (class "Default")
      (node (ref "JP1") (pin "28") (pinfunction "28_28") (pintype "passive"))
    )
    (net (code "149") (name "unconnected-(JP1-Pad29)") (class "Default")
      (node (ref "JP1") (pin "29") (pinfunction "29_29") (pintype "passive"))
    )
    (net (code "150") (name "unconnected-(JP1-Pad31)") (class "Default")
      (node (ref "JP1") (pin "31") (pinfunction "31_31") (pintype "passive"))
    )
    (net (code "151") (name "unconnected-(JP1-Pad32)") (class "Default")
      (node (ref "JP1") (pin "32") (pinfunction "32_32") (pintype "passive"))
    )
  )
)
